# media_player_v0001a.net
KiCad netlist of a schematic drawn in EAGLE
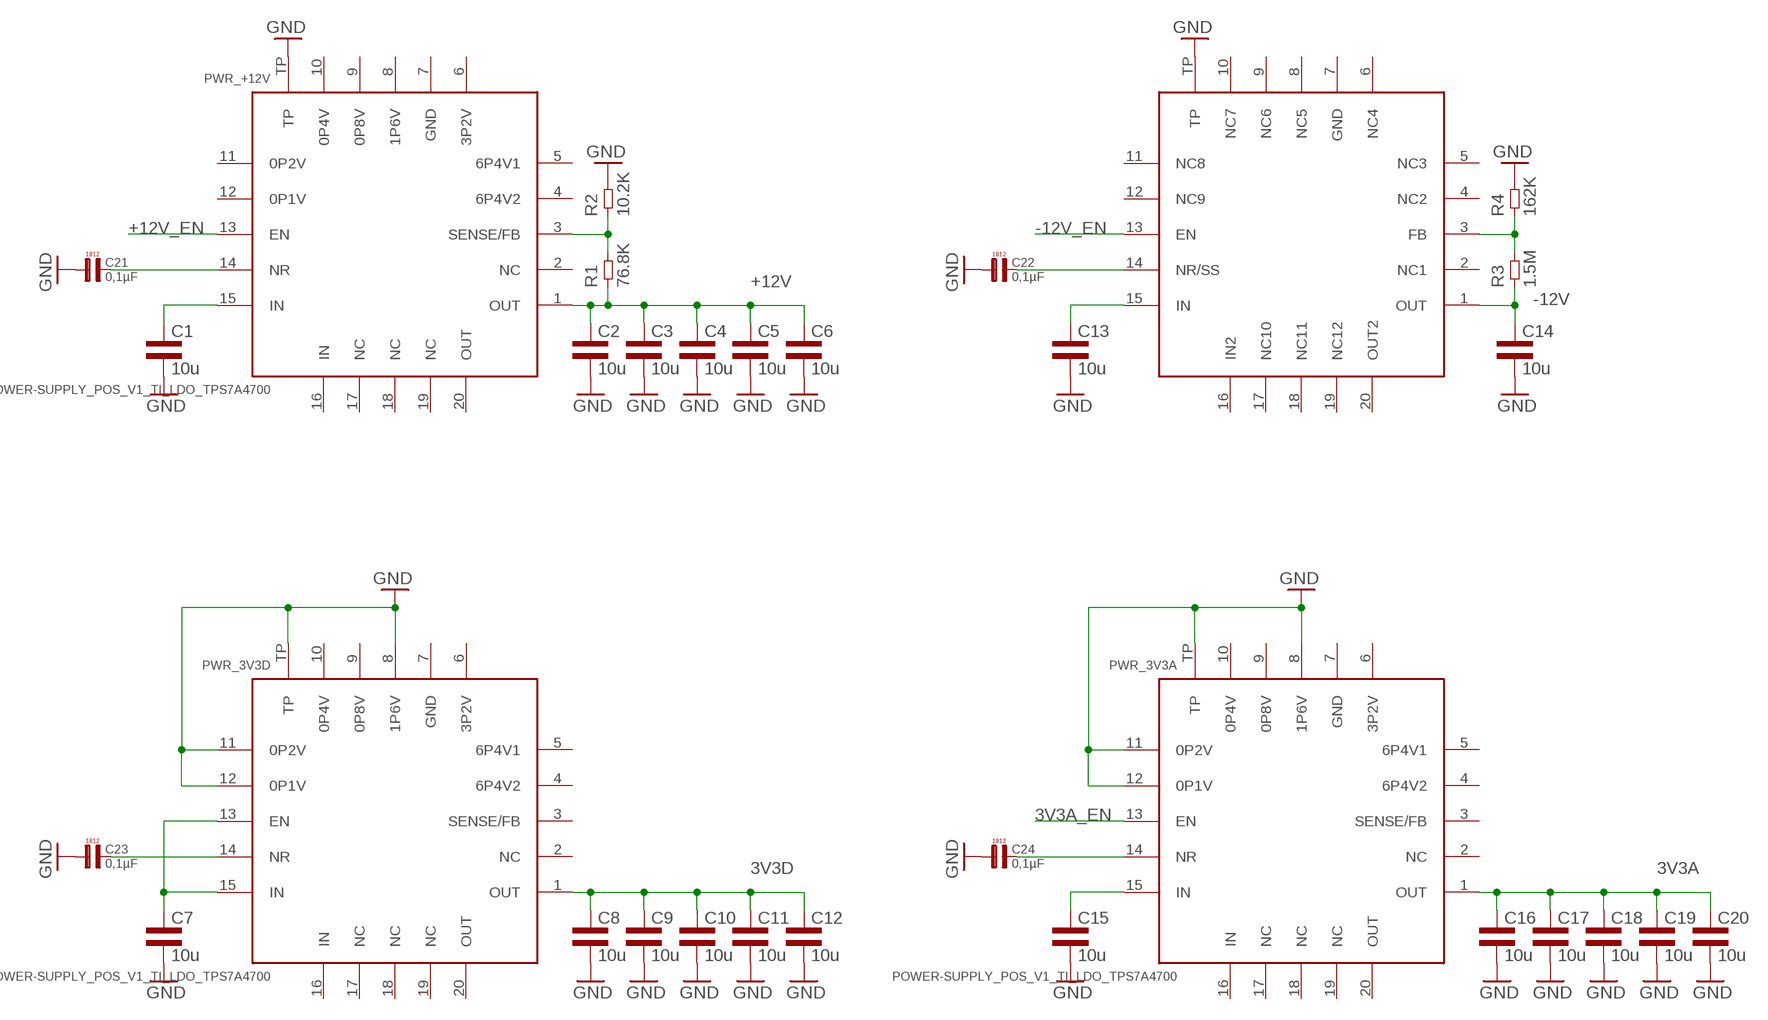
[diagram p0: schematic, sheet 1]
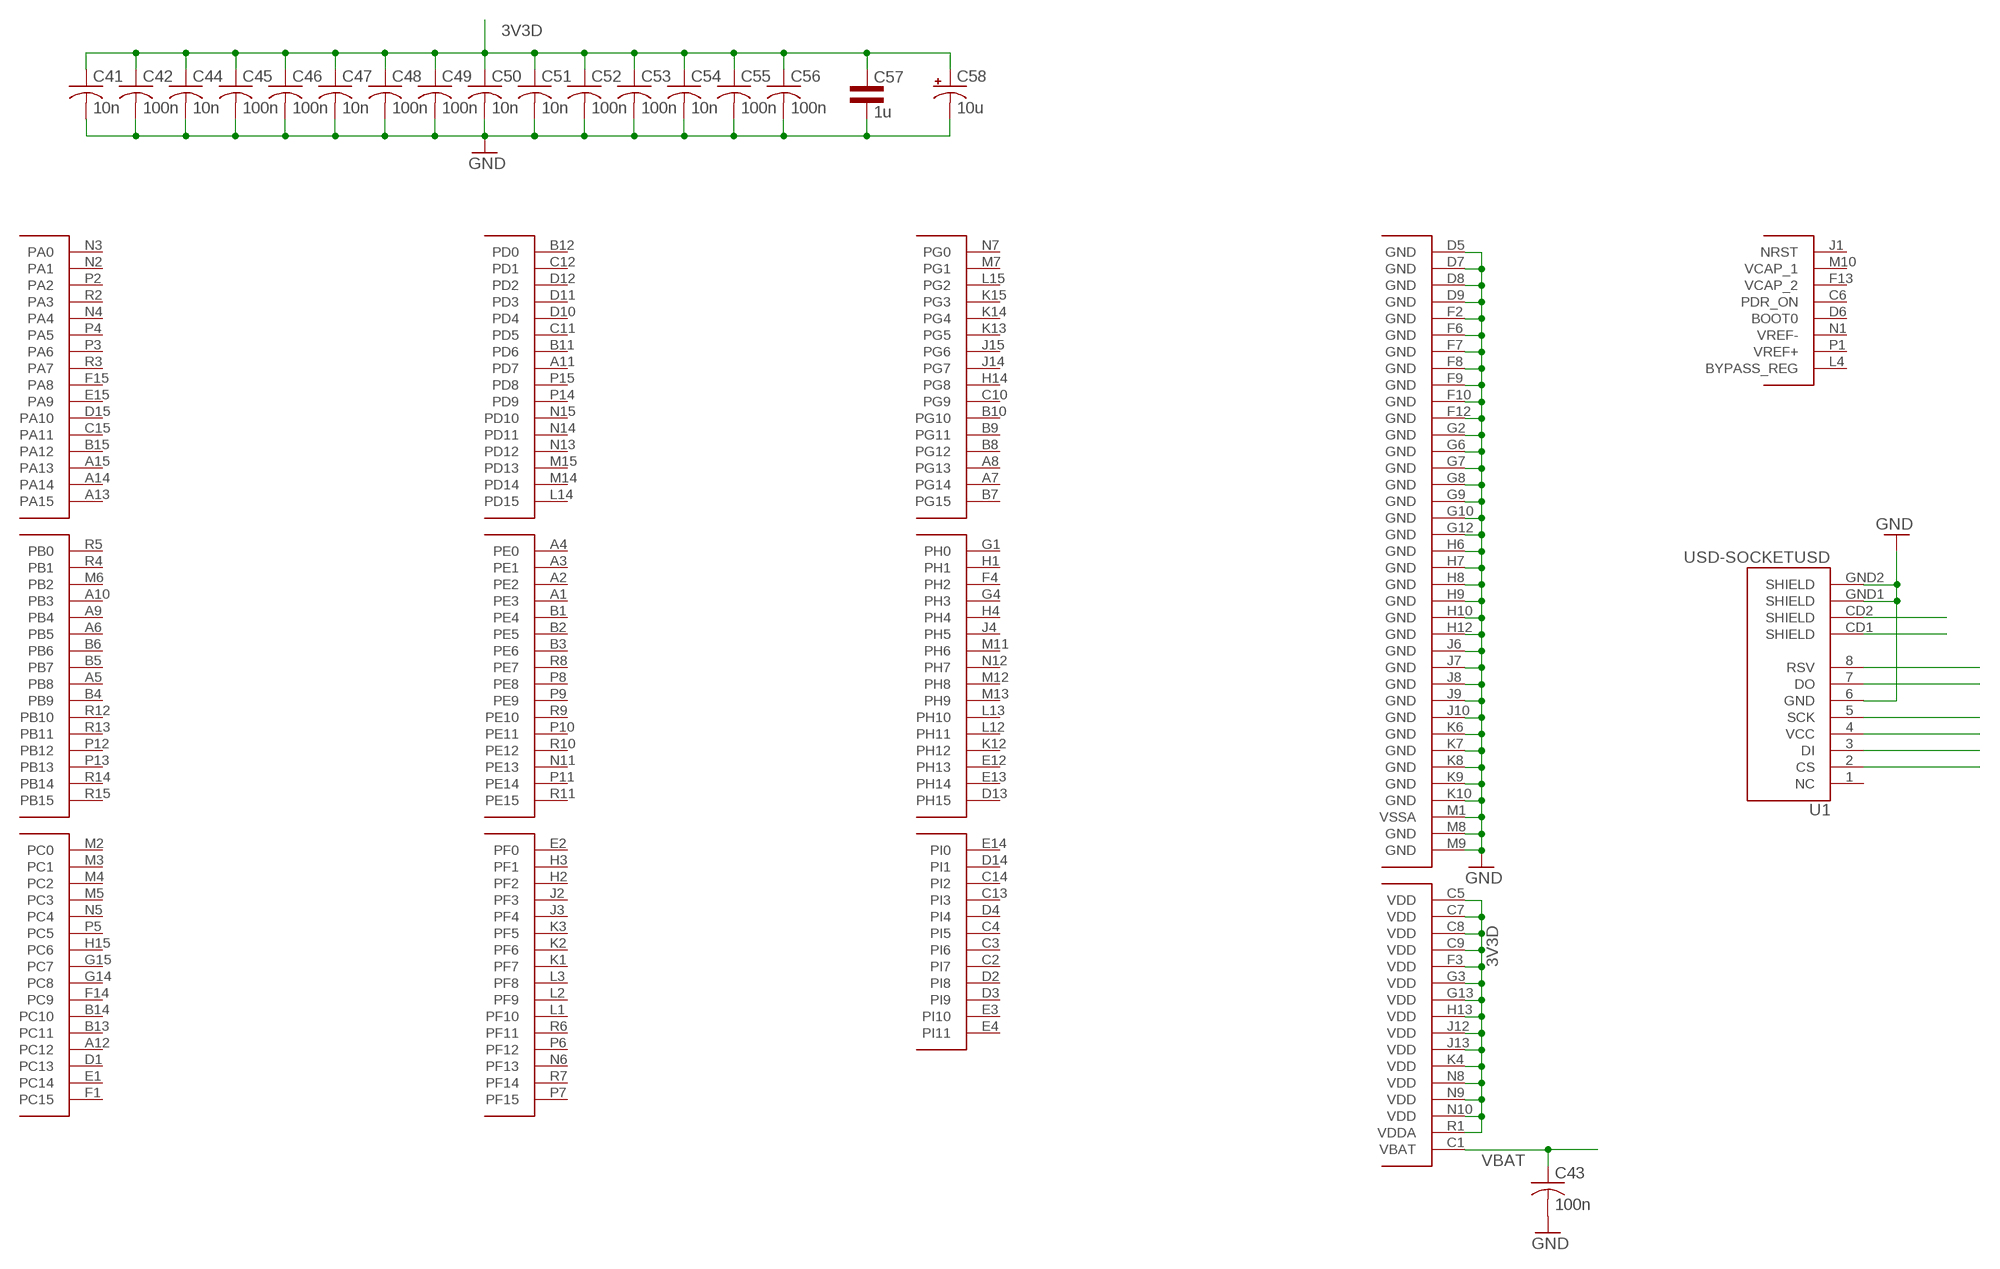
[diagram p1: schematic, sheet 2]
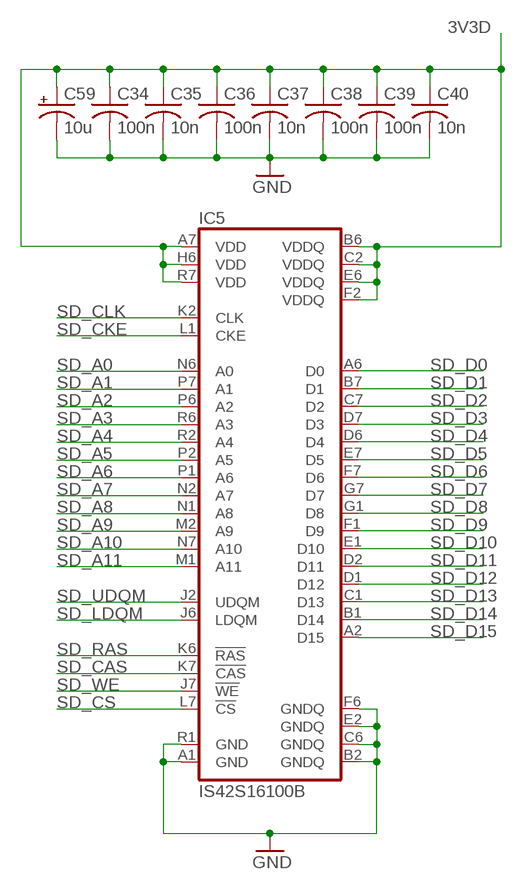
[diagram p2: schematic, sheet 3]
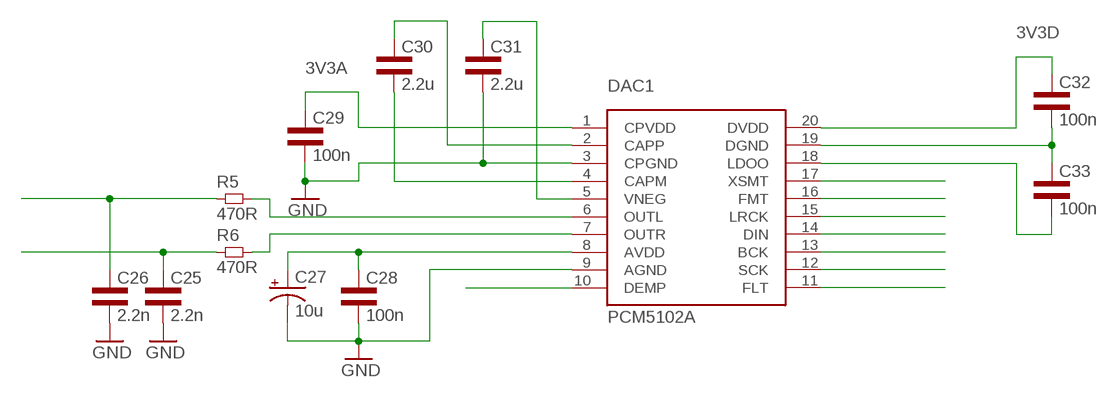
[diagram p3: schematic, sheet 4]
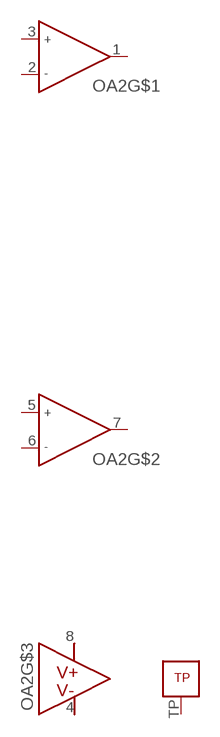
[diagram p4: schematic, sheet 5]
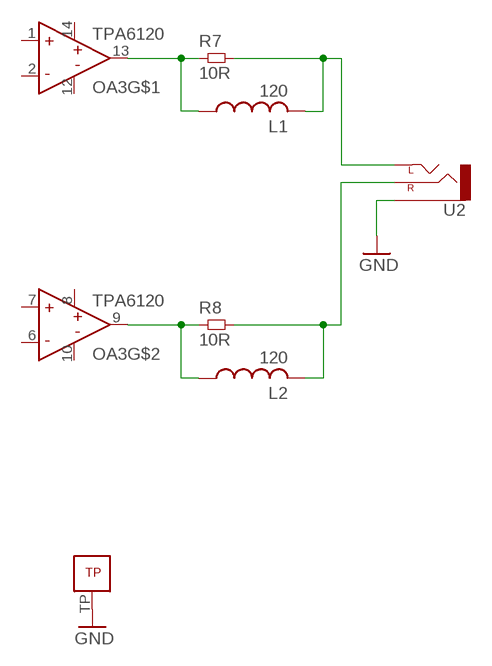
[diagram p5: schematic, sheet 6]

(export (version "E")
  (design (tool "Eeschema 10.0.6"))
  (components
    (comp (ref "C1")
      (value "10u")
      (footprint "eagle-import:0805L3")
      (libsource (lib "eagle-import") (part "CAP0805L3"))
    )
    (comp (ref "C2")
      (value "10u")
      (footprint "eagle-import:0805L3")
      (libsource (lib "eagle-import") (part "CAP0805L3"))
    )
    (comp (ref "C3")
      (value "10u")
      (footprint "eagle-import:0805L3")
      (libsource (lib "eagle-import") (part "CAP0805L3"))
    )
    (comp (ref "C4")
      (value "10u")
      (footprint "eagle-import:0805L3")
      (libsource (lib "eagle-import") (part "CAP0805L3"))
    )
    (comp (ref "C5")
      (value "10u")
      (footprint "eagle-import:0805L3")
      (libsource (lib "eagle-import") (part "CAP0805L3"))
    )
    (comp (ref "C6")
      (value "10u")
      (footprint "eagle-import:0805L3")
      (libsource (lib "eagle-import") (part "CAP0805L3"))
    )
    (comp (ref "C7")
      (value "10u")
      (footprint "eagle-import:0805L3")
      (libsource (lib "eagle-import") (part "CAP0805L3"))
    )
    (comp (ref "C8")
      (value "10u")
      (footprint "eagle-import:0805L3")
      (libsource (lib "eagle-import") (part "CAP0805L3"))
    )
    (comp (ref "C9")
      (value "10u")
      (footprint "eagle-import:0805L3")
      (libsource (lib "eagle-import") (part "CAP0805L3"))
    )
    (comp (ref "C10")
      (value "10u")
      (footprint "eagle-import:0805L3")
      (libsource (lib "eagle-import") (part "CAP0805L3"))
    )
    (comp (ref "C11")
      (value "10u")
      (footprint "eagle-import:0805L3")
      (libsource (lib "eagle-import") (part "CAP0805L3"))
    )
    (comp (ref "C12")
      (value "10u")
      (footprint "eagle-import:0805L3")
      (libsource (lib "eagle-import") (part "CAP0805L3"))
    )
    (comp (ref "C13")
      (value "10u")
      (footprint "eagle-import:0805L3")
      (libsource (lib "eagle-import") (part "CAP0805L3"))
    )
    (comp (ref "C14")
      (value "10u")
      (footprint "eagle-import:0805L3")
      (libsource (lib "eagle-import") (part "CAP0805L3"))
    )
    (comp (ref "C15")
      (value "10u")
      (footprint "eagle-import:0805L3")
      (libsource (lib "eagle-import") (part "CAP0805L3"))
    )
    (comp (ref "C16")
      (value "10u")
      (footprint "eagle-import:0805L3")
      (libsource (lib "eagle-import") (part "CAP0805L3"))
    )
    (comp (ref "C17")
      (value "10u")
      (footprint "eagle-import:0805L3")
      (libsource (lib "eagle-import") (part "CAP0805L3"))
    )
    (comp (ref "C18")
      (value "10u")
      (footprint "eagle-import:0805L3")
      (libsource (lib "eagle-import") (part "CAP0805L3"))
    )
    (comp (ref "C19")
      (value "10u")
      (footprint "eagle-import:0805L3")
      (libsource (lib "eagle-import") (part "CAP0805L3"))
    )
    (comp (ref "C20")
      (value "10u")
      (footprint "eagle-import:0805L3")
      (libsource (lib "eagle-import") (part "CAP0805L3"))
    )
    (comp (ref "C21")
      (value "0,1µF")
      (footprint "eagle-import:L4,8")
      (libsource (lib "eagle-import") (part "0,1µF"))
    )
    (comp (ref "C22")
      (value "0,1µF")
      (footprint "eagle-import:L4,8")
      (libsource (lib "eagle-import") (part "0,1µF"))
    )
    (comp (ref "C23")
      (value "0,1µF")
      (footprint "eagle-import:L4,8")
      (libsource (lib "eagle-import") (part "0,1µF"))
    )
    (comp (ref "C24")
      (value "0,1µF")
      (footprint "eagle-import:L4,8")
      (libsource (lib "eagle-import") (part "0,1µF"))
    )
    (comp (ref "PWR_+12V")
      (value "POWER-SUPPLY_POS_V1_TI_LDO_TPS7A4700")
      (footprint "eagle-import:POWER-SUPPLY_POS_V1_TI_LDO_VQFN-20")
      (libsource (lib "eagle-import") (part "POWER-SUPPLY_POS_V1_TI_LDO_TPS7A4700"))
    )
    (comp (ref "PWR_-12V")
      (value "POWER-SUPPLY_POS_V1_TI_LDO_TPS7A3301RGWT")
      (footprint "eagle-import:POWER-SUPPLY_POS_V1_TI_LDO_VQFN-20")
      (libsource (lib "eagle-import") (part "POWER-SUPPLY_POS_V1_TI_LDO_TPS7A3301RGWT"))
    )
    (comp (ref "PWR_3V3A")
      (value "POWER-SUPPLY_POS_V1_TI_LDO_TPS7A4700")
      (footprint "eagle-import:POWER-SUPPLY_POS_V1_TI_LDO_VQFN-20")
      (libsource (lib "eagle-import") (part "POWER-SUPPLY_POS_V1_TI_LDO_TPS7A4700"))
    )
    (comp (ref "PWR_3V3D")
      (value "POWER-SUPPLY_POS_V1_TI_LDO_TPS7A4700")
      (footprint "eagle-import:POWER-SUPPLY_POS_V1_TI_LDO_VQFN-20")
      (libsource (lib "eagle-import") (part "POWER-SUPPLY_POS_V1_TI_LDO_TPS7A4700"))
    )
    (comp (ref "R1")
      (value "76.8K")
      (footprint "eagle-import:0603L3")
      (libsource (lib "eagle-import") (part "RES0603L3"))
    )
    (comp (ref "R2")
      (value "10.2K")
      (footprint "eagle-import:0603L3")
      (libsource (lib "eagle-import") (part "RES0603L3"))
    )
    (comp (ref "R3")
      (value "1.5M")
      (footprint "eagle-import:0603L3")
      (libsource (lib "eagle-import") (part "RES0603L3"))
    )
    (comp (ref "R4")
      (value "162K")
      (footprint "eagle-import:0603L3")
      (libsource (lib "eagle-import") (part "RES0603L3"))
    )
    (comp (ref "OA2")
      (value "OPA1612")
      (footprint "eagle-import:S-PWSON-N8")
      (libsource (lib "eagle-import") (part "OPA1612"))
    )
    (comp (ref "C25")
      (value "2.2n")
      (footprint "eagle-import:0805L3")
      (libsource (lib "eagle-import") (part "CAP0805L3"))
    )
    (comp (ref "C26")
      (value "2.2n")
      (footprint "eagle-import:0805L3")
      (libsource (lib "eagle-import") (part "CAP0805L3"))
    )
    (comp (ref "C27")
      (value "10u")
      (footprint "eagle-import:A_3216-18R")
      (libsource (lib "eagle-import") (part "CPOL-USA/3216-18R"))
    )
    (comp (ref "C28")
      (value "100n")
      (footprint "eagle-import:0603L3")
      (libsource (lib "eagle-import") (part "CAP0603L3"))
    )
    (comp (ref "C29")
      (value "100n")
      (footprint "eagle-import:0603L3")
      (libsource (lib "eagle-import") (part "CAP0603L3"))
    )
    (comp (ref "C30")
      (value "2.2u")
      (footprint "eagle-import:0805L3")
      (libsource (lib "eagle-import") (part "CAP0805L3"))
    )
    (comp (ref "C31")
      (value "2.2u")
      (footprint "eagle-import:0805L3")
      (libsource (lib "eagle-import") (part "CAP0805L3"))
    )
    (comp (ref "C32")
      (value "100n")
      (footprint "eagle-import:0603L3")
      (libsource (lib "eagle-import") (part "CAP0603L3"))
    )
    (comp (ref "C33")
      (value "100n")
      (footprint "eagle-import:0603L3")
      (libsource (lib "eagle-import") (part "CAP0603L3"))
    )
    (comp (ref "DAC1")
      (value "PCM5102A")
      (footprint "eagle-import:R-PDSO-G20_65")
      (libsource (lib "eagle-import") (part "PCM5102A"))
    )
    (comp (ref "R5")
      (value "470R")
      (footprint "eagle-import:0805L3")
      (libsource (lib "eagle-import") (part "RES0805L3"))
    )
    (comp (ref "R6")
      (value "470R")
      (footprint "eagle-import:0805L3")
      (libsource (lib "eagle-import") (part "RES0805L3"))
    )
    (comp (ref "L1")
      (value "120")
      (footprint "eagle-import:L2012C")
      (libsource (lib "eagle-import") (part "L-USL2012C"))
    )
    (comp (ref "L2")
      (value "120")
      (footprint "eagle-import:L2012C")
      (libsource (lib "eagle-import") (part "L-USL2012C"))
    )
    (comp (ref "OA3")
      (value "TPA6120QFN")
      (footprint "eagle-import:S-PVQFN-N14")
      (libsource (lib "eagle-import") (part "TPA6120QFN"))
    )
    (comp (ref "R7")
      (value "10R")
      (footprint "eagle-import:0805L3")
      (libsource (lib "eagle-import") (part "RES0805L3"))
    )
    (comp (ref "R8")
      (value "10R")
      (footprint "eagle-import:0805L3")
      (libsource (lib "eagle-import") (part "RES0805L3"))
    )
    (comp (ref "U2")
      (value "AUDIO-JACKSMD2")
      (footprint "eagle-import:AUDIO-JACK-3.5MM-SMD")
      (libsource (lib "eagle-import") (part "AUDIO-JACKSMD2"))
    )
    (comp (ref "C41")
      (value "10n")
      (footprint "eagle-import:C0201")
      (libsource (lib "eagle-import") (part "C-USC0201"))
    )
    (comp (ref "C42")
      (value "100n")
      (footprint "eagle-import:C0201")
      (libsource (lib "eagle-import") (part "C-USC0201"))
    )
    (comp (ref "C43")
      (value "100n")
      (footprint "eagle-import:C0201")
      (libsource (lib "eagle-import") (part "C-USC0201"))
    )
    (comp (ref "C44")
      (value "10n")
      (footprint "eagle-import:C0201")
      (libsource (lib "eagle-import") (part "C-USC0201"))
    )
    (comp (ref "C45")
      (value "100n")
      (footprint "eagle-import:C0201")
      (libsource (lib "eagle-import") (part "C-USC0201"))
    )
    (comp (ref "C46")
      (value "100n")
      (footprint "eagle-import:C0201")
      (libsource (lib "eagle-import") (part "C-USC0201"))
    )
    (comp (ref "C47")
      (value "10n")
      (footprint "eagle-import:C0201")
      (libsource (lib "eagle-import") (part "C-USC0201"))
    )
    (comp (ref "C48")
      (value "100n")
      (footprint "eagle-import:C0201")
      (libsource (lib "eagle-import") (part "C-USC0201"))
    )
    (comp (ref "C49")
      (value "100n")
      (footprint "eagle-import:C0201")
      (libsource (lib "eagle-import") (part "C-USC0201"))
    )
    (comp (ref "C50")
      (value "10n")
      (footprint "eagle-import:C0201")
      (libsource (lib "eagle-import") (part "C-USC0201"))
    )
    (comp (ref "C51")
      (value "10n")
      (footprint "eagle-import:C0201")
      (libsource (lib "eagle-import") (part "C-USC0201"))
    )
    (comp (ref "C52")
      (value "100n")
      (footprint "eagle-import:C0201")
      (libsource (lib "eagle-import") (part "C-USC0201"))
    )
    (comp (ref "C53")
      (value "100n")
      (footprint "eagle-import:C0201")
      (libsource (lib "eagle-import") (part "C-USC0201"))
    )
    (comp (ref "C54")
      (value "10n")
      (footprint "eagle-import:C0201")
      (libsource (lib "eagle-import") (part "C-USC0201"))
    )
    (comp (ref "C55")
      (value "100n")
      (footprint "eagle-import:C0201")
      (libsource (lib "eagle-import") (part "C-USC0201"))
    )
    (comp (ref "C56")
      (value "100n")
      (footprint "eagle-import:C0201")
      (libsource (lib "eagle-import") (part "C-USC0201"))
    )
    (comp (ref "C57")
      (value "1u")
      (footprint "eagle-import:0805L3")
      (libsource (lib "eagle-import") (part "CAP0805L3"))
    )
    (comp (ref "C58")
      (value "10u")
      (footprint "eagle-import:A_3216-18R")
      (libsource (lib "eagle-import") (part "CPOL-USA/3216-18R"))
    )
    (comp (ref "U$1")
      (value "STM32_32BIT_MCU_STM32F407IG")
      (footprint "eagle-import:STM32_32BIT_MCU_UFBGA176+25")
      (libsource (lib "eagle-import") (part "STM32_32BIT_MCU_STM32F407IG"))
    )
    (comp (ref "U1")
      (value "USD-SOCKETUSD")
      (footprint "eagle-import:USD-SOCKET-PP")
      (libsource (lib "eagle-import") (part "USD-SOCKETUSD"))
    )
    (comp (ref "C34")
      (value "100n")
      (footprint "eagle-import:C0201")
      (libsource (lib "eagle-import") (part "C-USC0201"))
    )
    (comp (ref "C35")
      (value "10n")
      (footprint "eagle-import:C0201")
      (libsource (lib "eagle-import") (part "C-USC0201"))
    )
    (comp (ref "C36")
      (value "100n")
      (footprint "eagle-import:C0201")
      (libsource (lib "eagle-import") (part "C-USC0201"))
    )
    (comp (ref "C37")
      (value "10n")
      (footprint "eagle-import:C0201")
      (libsource (lib "eagle-import") (part "C-USC0201"))
    )
    (comp (ref "C38")
      (value "100n")
      (footprint "eagle-import:C0201")
      (libsource (lib "eagle-import") (part "C-USC0201"))
    )
    (comp (ref "C39")
      (value "100n")
      (footprint "eagle-import:C0201")
      (libsource (lib "eagle-import") (part "C-USC0201"))
    )
    (comp (ref "C40")
      (value "10n")
      (footprint "eagle-import:C0201")
      (libsource (lib "eagle-import") (part "C-USC0201"))
    )
    (comp (ref "C59")
      (value "10u")
      (footprint "eagle-import:A_3216-18R")
      (libsource (lib "eagle-import") (part "CPOL-USA/3216-18R"))
    )
    (comp (ref "IC5")
      (value "IS42S16100B")
      (footprint "eagle-import:MBGA60")
      (libsource (lib "eagle-import") (part "IS42S16100B"))
    )
  )
  (nets
    (net (code "1") (name "+12V_EN") (class "Default")
      (node (ref "PWR_+12V") (pin "13") (pinfunction "EN_13") (pintype "bidirectional"))
    )
    (net (code "2") (name "-12V_EN") (class "Default")
      (node (ref "PWR_-12V") (pin "13") (pinfunction "EN_13") (pintype "bidirectional"))
    )
    (net (code "3") (name "3V3A") (class "Default")
      (node (ref "C16") (pin "1") (pinfunction "1_1") (pintype "bidirectional"))
      (node (ref "C17") (pin "1") (pinfunction "1_1") (pintype "bidirectional"))
      (node (ref "C18") (pin "1") (pinfunction "1_1") (pintype "bidirectional"))
      (node (ref "C19") (pin "1") (pinfunction "1_1") (pintype "bidirectional"))
      (node (ref "C20") (pin "1") (pinfunction "1_1") (pintype "bidirectional"))
      (node (ref "C29") (pin "P$1") (pinfunction "1_P$1") (pintype "bidirectional"))
      (node (ref "DAC1") (pin "1") (pinfunction "CPVDD_1") (pintype "bidirectional"))
      (node (ref "PWR_3V3A") (pin "1") (pinfunction "OUT_1") (pintype "bidirectional"))
    )
    (net (code "4") (name "3V3A_EN") (class "Default")
      (node (ref "PWR_3V3A") (pin "13") (pinfunction "EN_13") (pintype "bidirectional"))
    )
    (net (code "5") (name "3V3D") (class "Default")
      (node (ref "C10") (pin "1") (pinfunction "1_1") (pintype "bidirectional"))
      (node (ref "C11") (pin "1") (pinfunction "1_1") (pintype "bidirectional"))
      (node (ref "C12") (pin "1") (pinfunction "1_1") (pintype "bidirectional"))
      (node (ref "C32") (pin "P$1") (pinfunction "1_P$1") (pintype "bidirectional"))
      (node (ref "C34") (pin "1") (pinfunction "1_1") (pintype "passive"))
      (node (ref "C35") (pin "1") (pinfunction "1_1") (pintype "passive"))
      (node (ref "C36") (pin "1") (pinfunction "1_1") (pintype "passive"))
      (node (ref "C37") (pin "1") (pinfunction "1_1") (pintype "passive"))
      (node (ref "C38") (pin "1") (pinfunction "1_1") (pintype "passive"))
      (node (ref "C39") (pin "1") (pinfunction "1_1") (pintype "passive"))
      (node (ref "C40") (pin "1") (pinfunction "1_1") (pintype "passive"))
      (node (ref "C41") (pin "1") (pinfunction "1_1") (pintype "passive"))
      (node (ref "C42") (pin "1") (pinfunction "1_1") (pintype "passive"))
      (node (ref "C44") (pin "1") (pinfunction "1_1") (pintype "passive"))
      (node (ref "C45") (pin "1") (pinfunction "1_1") (pintype "passive"))
      (node (ref "C46") (pin "1") (pinfunction "1_1") (pintype "passive"))
      (node (ref "C47") (pin "1") (pinfunction "1_1") (pintype "passive"))
      (node (ref "C48") (pin "1") (pinfunction "1_1") (pintype "passive"))
      (node (ref "C49") (pin "1") (pinfunction "1_1") (pintype "passive"))
      (node (ref "C50") (pin "1") (pinfunction "1_1") (pintype "passive"))
      (node (ref "C51") (pin "1") (pinfunction "1_1") (pintype "passive"))
      (node (ref "C52") (pin "1") (pinfunction "1_1") (pintype "passive"))
      (node (ref "C53") (pin "1") (pinfunction "1_1") (pintype "passive"))
      (node (ref "C54") (pin "1") (pinfunction "1_1") (pintype "passive"))
      (node (ref "C55") (pin "1") (pinfunction "1_1") (pintype "passive"))
      (node (ref "C56") (pin "1") (pinfunction "1_1") (pintype "passive"))
      (node (ref "C57") (pin "1") (pinfunction "1_1") (pintype "bidirectional"))
      (node (ref "C58") (pin "+") (pinfunction "+_+") (pintype "passive"))
      (node (ref "C59") (pin "+") (pinfunction "+_+") (pintype "passive"))
      (node (ref "C8") (pin "1") (pinfunction "1_1") (pintype "bidirectional"))
      (node (ref "C9") (pin "1") (pinfunction "1_1") (pintype "bidirectional"))
      (node (ref "DAC1") (pin "20") (pinfunction "DVDD_20") (pintype "bidirectional"))
      (node (ref "IC5") (pin "A7") (pinfunction "VDD_A7") (pintype "power_in"))
      (node (ref "IC5") (pin "B6") (pinfunction "VDDQ_B6") (pintype "power_in"))
      (node (ref "IC5") (pin "C2") (pinfunction "VDDQ_C2") (pintype "power_in"))
      (node (ref "IC5") (pin "E6") (pinfunction "VDDQ_E6") (pintype "power_in"))
      (node (ref "IC5") (pin "F2") (pinfunction "VDDQ_F2") (pintype "power_in"))
      (node (ref "IC5") (pin "H6") (pinfunction "VDD_H6") (pintype "power_in"))
      (node (ref "IC5") (pin "R7") (pinfunction "VDD_R7") (pintype "power_in"))
      (node (ref "PWR_3V3D") (pin "1") (pinfunction "OUT_1") (pintype "bidirectional"))
      (node (ref "U$1") (pin "C5") (pinfunction "VDD_C5") (pintype "bidirectional"))
      (node (ref "U$1") (pin "C7") (pinfunction "VDD_C7") (pintype "bidirectional"))
      (node (ref "U$1") (pin "C8") (pinfunction "VDD_C8") (pintype "bidirectional"))
      (node (ref "U$1") (pin "C9") (pinfunction "VDD_C9") (pintype "bidirectional"))
      (node (ref "U$1") (pin "F3") (pinfunction "VDD_F3") (pintype "bidirectional"))
      (node (ref "U$1") (pin "G13") (pinfunction "VDD_G13") (pintype "bidirectional"))
      (node (ref "U$1") (pin "G3") (pinfunction "VDD_G3") (pintype "bidirectional"))
      (node (ref "U$1") (pin "H13") (pinfunction "VDD_H13") (pintype "bidirectional"))
      (node (ref "U$1") (pin "J12") (pinfunction "VDD_J12") (pintype "bidirectional"))
      (node (ref "U$1") (pin "J13") (pinfunction "VDD_J13") (pintype "bidirectional"))
      (node (ref "U$1") (pin "K4") (pinfunction "VDD_K4") (pintype "bidirectional"))
      (node (ref "U$1") (pin "N10") (pinfunction "VDD_N10") (pintype "bidirectional"))
      (node (ref "U$1") (pin "N8") (pinfunction "VDD_N8") (pintype "bidirectional"))
      (node (ref "U$1") (pin "N9") (pinfunction "VDD_N9") (pintype "bidirectional"))
      (node (ref "U$1") (pin "R1") (pinfunction "VDDA_R1") (pintype "bidirectional"))
    )
    (net (code "6") (name "GND") (class "Default")
      (node (ref "C1") (pin "2") (pinfunction "2_2") (pintype "bidirectional"))
      (node (ref "C10") (pin "2") (pinfunction "2_2") (pintype "bidirectional"))
      (node (ref "C11") (pin "2") (pinfunction "2_2") (pintype "bidirectional"))
      (node (ref "C12") (pin "2") (pinfunction "2_2") (pintype "bidirectional"))
      (node (ref "C13") (pin "2") (pinfunction "2_2") (pintype "bidirectional"))
      (node (ref "C14") (pin "2") (pinfunction "2_2") (pintype "bidirectional"))
      (node (ref "C15") (pin "2") (pinfunction "2_2") (pintype "bidirectional"))
      (node (ref "C16") (pin "2") (pinfunction "2_2") (pintype "bidirectional"))
      (node (ref "C17") (pin "2") (pinfunction "2_2") (pintype "bidirectional"))
      (node (ref "C18") (pin "2") (pinfunction "2_2") (pintype "bidirectional"))
      (node (ref "C19") (pin "2") (pinfunction "2_2") (pintype "bidirectional"))
      (node (ref "C2") (pin "2") (pinfunction "2_2") (pintype "bidirectional"))
      (node (ref "C20") (pin "2") (pinfunction "2_2") (pintype "bidirectional"))
      (node (ref "C21") (pin "P$1") (pinfunction "1_P$1") (pintype "passive"))
      (node (ref "C22") (pin "P$1") (pinfunction "1_P$1") (pintype "passive"))
      (node (ref "C23") (pin "P$1") (pinfunction "1_P$1") (pintype "passive"))
      (node (ref "C24") (pin "P$1") (pinfunction "1_P$1") (pintype "passive"))
      (node (ref "C25") (pin "2") (pinfunction "2_2") (pintype "bidirectional"))
      (node (ref "C26") (pin "2") (pinfunction "2_2") (pintype "bidirectional"))
      (node (ref "C27") (pin "-") (pinfunction "-_-") (pintype "passive"))
      (node (ref "C28") (pin "P$2") (pinfunction "2_P$2") (pintype "bidirectional"))
      (node (ref "C29") (pin "P$2") (pinfunction "2_P$2") (pintype "bidirectional"))
      (node (ref "C3") (pin "2") (pinfunction "2_2") (pintype "bidirectional"))
      (node (ref "C31") (pin "2") (pinfunction "2_2") (pintype "bidirectional"))
      (node (ref "C34") (pin "2") (pinfunction "2_2") (pintype "passive"))
      (node (ref "C35") (pin "2") (pinfunction "2_2") (pintype "passive"))
      (node (ref "C36") (pin "2") (pinfunction "2_2") (pintype "passive"))
      (node (ref "C37") (pin "2") (pinfunction "2_2") (pintype "passive"))
      (node (ref "C38") (pin "2") (pinfunction "2_2") (pintype "passive"))
      (node (ref "C39") (pin "2") (pinfunction "2_2") (pintype "passive"))
      (node (ref "C4") (pin "2") (pinfunction "2_2") (pintype "bidirectional"))
      (node (ref "C40") (pin "2") (pinfunction "2_2") (pintype "passive"))
      (node (ref "C41") (pin "2") (pinfunction "2_2") (pintype "passive"))
      (node (ref "C42") (pin "2") (pinfunction "2_2") (pintype "passive"))
      (node (ref "C43") (pin "2") (pinfunction "2_2") (pintype "passive"))
      (node (ref "C44") (pin "2") (pinfunction "2_2") (pintype "passive"))
      (node (ref "C45") (pin "2") (pinfunction "2_2") (pintype "passive"))
      (node (ref "C46") (pin "2") (pinfunction "2_2") (pintype "passive"))
      (node (ref "C47") (pin "2") (pinfunction "2_2") (pintype "passive"))
      (node (ref "C48") (pin "2") (pinfunction "2_2") (pintype "passive"))
      (node (ref "C49") (pin "2") (pinfunction "2_2") (pintype "passive"))
      (node (ref "C5") (pin "2") (pinfunction "2_2") (pintype "bidirectional"))
      (node (ref "C50") (pin "2") (pinfunction "2_2") (pintype "passive"))
      (node (ref "C51") (pin "2") (pinfunction "2_2") (pintype "passive"))
      (node (ref "C52") (pin "2") (pinfunction "2_2") (pintype "passive"))
      (node (ref "C53") (pin "2") (pinfunction "2_2") (pintype "passive"))
      (node (ref "C54") (pin "2") (pinfunction "2_2") (pintype "passive"))
      (node (ref "C55") (pin "2") (pinfunction "2_2") (pintype "passive"))
      (node (ref "C56") (pin "2") (pinfunction "2_2") (pintype "passive"))
      (node (ref "C57") (pin "2") (pinfunction "2_2") (pintype "bidirectional"))
      (node (ref "C58") (pin "-") (pinfunction "-_-") (pintype "passive"))
      (node (ref "C59") (pin "-") (pinfunction "-_-") (pintype "passive"))
      (node (ref "C6") (pin "2") (pinfunction "2_2") (pintype "bidirectional"))
      (node (ref "C7") (pin "2") (pinfunction "2_2") (pintype "bidirectional"))
      (node (ref "C8") (pin "2") (pinfunction "2_2") (pintype "bidirectional"))
      (node (ref "C9") (pin "2") (pinfunction "2_2") (pintype "bidirectional"))
      (node (ref "DAC1") (pin "3") (pinfunction "CPGND_3") (pintype "bidirectional"))
      (node (ref "DAC1") (pin "9") (pinfunction "AGND_9") (pintype "bidirectional"))
      (node (ref "IC5") (pin "A1") (pinfunction "GND_A1") (pintype "power_in"))
      (node (ref "IC5") (pin "B2") (pinfunction "GNDQ_B2") (pintype "power_in"))
      (node (ref "IC5") (pin "C6") (pinfunction "GNDQ_C6") (pintype "power_in"))
      (node (ref "IC5") (pin "E2") (pinfunction "GNDQ_E2") (pintype "power_in"))
      (node (ref "IC5") (pin "F6") (pinfunction "GNDQ_F6") (pintype "power_in"))
      (node (ref "IC5") (pin "R1") (pinfunction "GND_R1") (pintype "power_in"))
      (node (ref "OA3") (pin "TP") (pinfunction "TP_TP") (pintype "bidirectional"))
      (node (ref "PWR_+12V") (pin "TP") (pinfunction "TP_TP") (pintype "bidirectional"))
      (node (ref "PWR_-12V") (pin "TP") (pinfunction "TP_TP") (pintype "bidirectional"))
      (node (ref "PWR_3V3A") (pin "11") (pinfunction "0P2V_11") (pintype "bidirectional"))
      (node (ref "PWR_3V3A") (pin "12") (pinfunction "0P1V_12") (pintype "bidirectional"))
      (node (ref "PWR_3V3A") (pin "8") (pinfunction "1P6V_8") (pintype "bidirectional"))
      (node (ref "PWR_3V3A") (pin "TP") (pinfunction "TP_TP") (pintype "bidirectional"))
      (node (ref "PWR_3V3D") (pin "11") (pinfunction "0P2V_11") (pintype "bidirectional"))
      (node (ref "PWR_3V3D") (pin "12") (pinfunction "0P1V_12") (pintype "bidirectional"))
      (node (ref "PWR_3V3D") (pin "8") (pinfunction "1P6V_8") (pintype "bidirectional"))
      (node (ref "PWR_3V3D") (pin "TP") (pinfunction "TP_TP") (pintype "bidirectional"))
      (node (ref "R2") (pin "P$2") (pinfunction "2_P$2") (pintype "bidirectional"))
      (node (ref "R4") (pin "P$2") (pinfunction "2_P$2") (pintype "bidirectional"))
      (node (ref "U$1") (pin "D5") (pinfunction "GND_D5") (pintype "bidirectional"))
      (node (ref "U$1") (pin "D7") (pinfunction "GND_D7") (pintype "bidirectional"))
      (node (ref "U$1") (pin "D8") (pinfunction "GND_D8") (pintype "bidirectional"))
      (node (ref "U$1") (pin "D9") (pinfunction "GND_D9") (pintype "bidirectional"))
      (node (ref "U$1") (pin "F10") (pinfunction "GND_F10") (pintype "bidirectional"))
      (node (ref "U$1") (pin "F12") (pinfunction "GND_F12") (pintype "bidirectional"))
      (node (ref "U$1") (pin "F2") (pinfunction "GND_F2") (pintype "bidirectional"))
      (node (ref "U$1") (pin "F6") (pinfunction "GND_F6") (pintype "bidirectional"))
      (node (ref "U$1") (pin "F7") (pinfunction "GND_F7") (pintype "bidirectional"))
      (node (ref "U$1") (pin "F8") (pinfunction "GND_F8") (pintype "bidirectional"))
      (node (ref "U$1") (pin "F9") (pinfunction "GND_F9") (pintype "bidirectional"))
      (node (ref "U$1") (pin "G10") (pinfunction "GND_G10") (pintype "bidirectional"))
      (node (ref "U$1") (pin "G12") (pinfunction "GND_G12") (pintype "bidirectional"))
      (node (ref "U$1") (pin "G2") (pinfunction "GND_G2") (pintype "bidirectional"))
      (node (ref "U$1") (pin "G6") (pinfunction "GND_G6") (pintype "bidirectional"))
      (node (ref "U$1") (pin "G7") (pinfunction "GND_G7") (pintype "bidirectional"))
      (node (ref "U$1") (pin "G8") (pinfunction "GND_G8") (pintype "bidirectional"))
      (node (ref "U$1") (pin "G9") (pinfunction "GND_G9") (pintype "bidirectional"))
      (node (ref "U$1") (pin "H10") (pinfunction "GND_H10") (pintype "bidirectional"))
      (node (ref "U$1") (pin "H12") (pinfunction "GND_H12") (pintype "bidirectional"))
      (node (ref "U$1") (pin "H6") (pinfunction "GND_H6") (pintype "bidirectional"))
      (node (ref "U$1") (pin "H7") (pinfunction "GND_H7") (pintype "bidirectional"))
      (node (ref "U$1") (pin "H8") (pinfunction "GND_H8") (pintype "bidirectional"))
      (node (ref "U$1") (pin "H9") (pinfunction "GND_H9") (pintype "bidirectional"))
      (node (ref "U$1") (pin "J10") (pinfunction "GND_J10") (pintype "bidirectional"))
      (node (ref "U$1") (pin "J6") (pinfunction "GND_J6") (pintype "bidirectional"))
      (node (ref "U$1") (pin "J7") (pinfunction "GND_J7") (pintype "bidirectional"))
      (node (ref "U$1") (pin "J8") (pinfunction "GND_J8") (pintype "bidirectional"))
      (node (ref "U$1") (pin "J9") (pinfunction "GND_J9") (pintype "bidirectional"))
      (node (ref "U$1") (pin "K10") (pinfunction "GND_K10") (pintype "bidirectional"))
      (node (ref "U$1") (pin "K6") (pinfunction "GND_K6") (pintype "bidirectional"))
      (node (ref "U$1") (pin "K7") (pinfunction "GND_K7") (pintype "bidirectional"))
      (node (ref "U$1") (pin "K8") (pinfunction "GND_K8") (pintype "bidirectional"))
      (node (ref "U$1") (pin "K9") (pinfunction "GND_K9") (pintype "bidirectional"))
      (node (ref "U$1") (pin "M1") (pinfunction "VSSA_M1") (pintype "bidirectional"))
      (node (ref "U$1") (pin "M8") (pinfunction "GND_M8") (pintype "bidirectional"))
      (node (ref "U$1") (pin "M9") (pinfunction "GND_M9") (pintype "bidirectional"))
      (node (ref "U1") (pin "6") (pinfunction "GND_6") (pintype "bidirectional"))
      (node (ref "U1") (pin "GND1") (pinfunction "SHIELD_GND1") (pintype "bidirectional"))
      (node (ref "U1") (pin "GND2") (pinfunction "SHIELD_GND2") (pintype "bidirectional"))
      (node (ref "U2") (pin "SLEEVE") (pinfunction "SLEEVE_SLEEVE") (pintype "bidirectional"))
    )
    (net (code "7") (name "Net-(C21-2)") (class "Default")
      (node (ref "C21") (pin "P$2") (pinfunction "2_P$2") (pintype "passive"))
      (node (ref "PWR_+12V") (pin "14") (pinfunction "NR_14") (pintype "bidirectional"))
    )
    (net (code "8") (name "Net-(C22-2)") (class "Default")
      (node (ref "C22") (pin "P$2") (pinfunction "2_P$2") (pintype "passive"))
      (node (ref "PWR_-12V") (pin "14") (pinfunction "NR/SS_14") (pintype "bidirectional"))
    )
    (net (code "9") (name "Net-(C23-2)") (class "Default")
      (node (ref "C23") (pin "P$2") (pinfunction "2_P$2") (pintype "passive"))
      (node (ref "PWR_3V3D") (pin "14") (pinfunction "NR_14") (pintype "bidirectional"))
    )
    (net (code "10") (name "Net-(C24-2)") (class "Default")
      (node (ref "C24") (pin "P$2") (pinfunction "2_P$2") (pintype "passive"))
      (node (ref "PWR_3V3A") (pin "14") (pinfunction "NR_14") (pintype "bidirectional"))
    )
    (net (code "11") (name "Net-(C25-Pad1)") (class "Default")
      (node (ref "C25") (pin "1") (pinfunction "1_1") (pintype "bidirectional"))
      (node (ref "R6") (pin "1") (pinfunction "1_1") (pintype "bidirectional"))
    )
    (net (code "12") (name "Net-(C26-Pad1)") (class "Default")
      (node (ref "C26") (pin "1") (pinfunction "1_1") (pintype "bidirectional"))
      (node (ref "R5") (pin "1") (pinfunction "1_1") (pintype "bidirectional"))
    )
    (net (code "13") (name "Net-(C28-1)") (class "Default")
      (node (ref "C27") (pin "+") (pinfunction "+_+") (pintype "passive"))
      (node (ref "C28") (pin "P$1") (pinfunction "1_P$1") (pintype "bidirectional"))
      (node (ref "DAC1") (pin "8") (pinfunction "AVDD_8") (pintype "bidirectional"))
    )
    (net (code "14") (name "Net-(C32-2)") (class "Default")
      (node (ref "C32") (pin "P$2") (pinfunction "2_P$2") (pintype "bidirectional"))
      (node (ref "C33") (pin "P$1") (pinfunction "1_P$1") (pintype "bidirectional"))
      (node (ref "DAC1") (pin "19") (pinfunction "DGND_19") (pintype "bidirectional"))
    )
    (net (code "15") (name "Net-(C33-2)") (class "Default")
      (node (ref "C33") (pin "P$2") (pinfunction "2_P$2") (pintype "bidirectional"))
      (node (ref "DAC1") (pin "18") (pinfunction "LDOO_18") (pintype "bidirectional"))
    )
    (net (code "16") (name "Net-(DAC1-CAPM)") (class "Default")
      (node (ref "C30") (pin "2") (pinfunction "2_2") (pintype "bidirectional"))
      (node (ref "DAC1") (pin "4") (pinfunction "CAPM_4") (pintype "bidirectional"))
    )
    (net (code "17") (name "Net-(DAC1-CAPP)") (class "Default")
      (node (ref "C30") (pin "1") (pinfunction "1_1") (pintype "bidirectional"))
      (node (ref "DAC1") (pin "2") (pinfunction "CAPP_2") (pintype "bidirectional"))
    )
    (net (code "18") (name "Net-(DAC1-OUTL)") (class "Default")
      (node (ref "DAC1") (pin "6") (pinfunction "OUTL_6") (pintype "bidirectional"))
      (node (ref "R5") (pin "2") (pinfunction "2_2") (pintype "bidirectional"))
    )
    (net (code "19") (name "Net-(DAC1-OUTR)") (class "Default")
      (node (ref "DAC1") (pin "7") (pinfunction "OUTR_7") (pintype "bidirectional"))
      (node (ref "R6") (pin "2") (pinfunction "2_2") (pintype "bidirectional"))
    )
    (net (code "20") (name "Net-(DAC1-VNEG)") (class "Default")
      (node (ref "C31") (pin "1") (pinfunction "1_1") (pintype "bidirectional"))
      (node (ref "DAC1") (pin "5") (pinfunction "VNEG_5") (pintype "bidirectional"))
    )
    (net (code "21") (name "Net-(OA3A-OUT)") (class "Default")
      (node (ref "L1") (pin "1") (pinfunction "1_1") (pintype "passive"))
      (node (ref "OA3") (pin "13") (pinfunction "OUT_13") (pintype "bidirectional"))
      (node (ref "R7") (pin "1") (pinfunction "1_1") (pintype "bidirectional"))
    )
    (net (code "22") (name "Net-(OA3B-OUT)") (class "Default")
      (node (ref "L2") (pin "1") (pinfunction "1_1") (pintype "passive"))
      (node (ref "OA3") (pin "9") (pinfunction "OUT_9") (pintype "bidirectional"))
      (node (ref "R8") (pin "1") (pinfunction "1_1") (pintype "bidirectional"))
    )
    (net (code "23") (name "Net-(PWR_+12V-SENSE{slash}FB)") (class "Default")
      (node (ref "PWR_+12V") (pin "3") (pinfunction "SENSE/FB_3") (pintype "bidirectional"))
      (node (ref "R1") (pin "P$2") (pinfunction "2_P$2") (pintype "bidirectional"))
      (node (ref "R2") (pin "P$1") (pinfunction "1_P$1") (pintype "bidirectional"))
    )
    (net (code "24") (name "Net-(PWR_-12V-FB)") (class "Default")
      (node (ref "PWR_-12V") (pin "3") (pinfunction "FB_3") (pintype "bidirectional"))
      (node (ref "R3") (pin "P$2") (pinfunction "2_P$2") (pintype "bidirectional"))
      (node (ref "R4") (pin "P$1") (pinfunction "1_P$1") (pintype "bidirectional"))
    )
    (net (code "25") (name "Net-(PWR_-12V-OUT)") (class "Default")
      (node (ref "C14") (pin "1") (pinfunction "1_1") (pintype "bidirectional"))
      (node (ref "PWR_-12V") (pin "1") (pinfunction "OUT_1") (pintype "bidirectional"))
      (node (ref "R3") (pin "P$1") (pinfunction "1_P$1") (pintype "bidirectional"))
    )
    (net (code "26") (name "Net-(R1-1)") (class "Default")
      (node (ref "C2") (pin "1") (pinfunction "1_1") (pintype "bidirectional"))
      (node (ref "C3") (pin "1") (pinfunction "1_1") (pintype "bidirectional"))
      (node (ref "C4") (pin "1") (pinfunction "1_1") (pintype "bidirectional"))
      (node (ref "C5") (pin "1") (pinfunction "1_1") (pintype "bidirectional"))
      (node (ref "C6") (pin "1") (pinfunction "1_1") (pintype "bidirectional"))
      (node (ref "PWR_+12V") (pin "1") (pinfunction "OUT_1") (pintype "bidirectional"))
      (node (ref "R1") (pin "P$1") (pinfunction "1_P$1") (pintype "bidirectional"))
    )
    (net (code "27") (name "Net-(U2-LEFT)") (class "Default")
      (node (ref "L1") (pin "2") (pinfunction "2_2") (pintype "passive"))
      (node (ref "R7") (pin "2") (pinfunction "2_2") (pintype "bidirectional"))
      (node (ref "U2") (pin "TIP") (pinfunction "LEFT_TIP") (pintype "bidirectional"))
    )
    (net (code "28") (name "Net-(U2-RIGHT)") (class "Default")
      (node (ref "L2") (pin "2") (pinfunction "2_2") (pintype "passive"))
      (node (ref "R8") (pin "2") (pinfunction "2_2") (pintype "bidirectional"))
      (node (ref "U2") (pin "RING") (pinfunction "RIGHT_RING") (pintype "bidirectional"))
    )
    (net (code "29") (name "SD_A0") (class "Default")
      (node (ref "IC5") (pin "N6") (pinfunction "A0_N6") (pintype "input"))
    )
    (net (code "30") (name "SD_A1") (class "Default")
      (node (ref "IC5") (pin "P7") (pinfunction "A1_P7") (pintype "input"))
    )
    (net (code "31") (name "SD_A2") (class "Default")
      (node (ref "IC5") (pin "P6") (pinfunction "A2_P6") (pintype "input"))
    )
    (net (code "32") (name "SD_A3") (class "Default")
      (node (ref "IC5") (pin "R6") (pinfunction "A3_R6") (pintype "input"))
    )
    (net (code "33") (name "SD_A4") (class "Default")
      (node (ref "IC5") (pin "R2") (pinfunction "A4_R2") (pintype "input"))
    )
    (net (code "34") (name "SD_A5") (class "Default")
      (node (ref "IC5") (pin "P2") (pinfunction "A5_P2") (pintype "input"))
    )
    (net (code "35") (name "SD_A6") (class "Default")
      (node (ref "IC5") (pin "P1") (pinfunction "A6_P1") (pintype "input"))
    )
    (net (code "36") (name "SD_A7") (class "Default")
      (node (ref "IC5") (pin "N2") (pinfunction "A7_N2") (pintype "input"))
    )
    (net (code "37") (name "SD_A8") (class "Default")
      (node (ref "IC5") (pin "N1") (pinfunction "A8_N1") (pintype "input"))
    )
    (net (code "38") (name "SD_A9") (class "Default")
      (node (ref "IC5") (pin "M2") (pinfunction "A9_M2") (pintype "input"))
    )
    (net (code "39") (name "SD_A10") (class "Default")
      (node (ref "IC5") (pin "N7") (pinfunction "A10_N7") (pintype "input"))
    )
    (net (code "40") (name "SD_A11") (class "Default")
      (node (ref "IC5") (pin "M1") (pinfunction "A11_M1") (pintype "input"))
    )
    (net (code "41") (name "SD_CAS") (class "Default")
      (node (ref "IC5") (pin "K7") (pinfunction "~{CAS}_K7") (pintype "input"))
    )
    (net (code "42") (name "SD_CKE") (class "Default")
      (node (ref "IC5") (pin "L1") (pinfunction "CKE_L1") (pintype "input"))
    )
    (net (code "43") (name "SD_CLK") (class "Default")
      (node (ref "IC5") (pin "K2") (pinfunction "CLK_K2") (pintype "input"))
    )
    (net (code "44") (name "SD_CS") (class "Default")
      (node (ref "IC5") (pin "L7") (pinfunction "~{CS}_L7") (pintype "input"))
    )
    (net (code "45") (name "SD_D0") (class "Default")
      (node (ref "IC5") (pin "A6") (pinfunction "D0_A6") (pintype "bidirectional"))
    )
    (net (code "46") (name "SD_D1") (class "Default")
      (node (ref "IC5") (pin "B7") (pinfunction "D1_B7") (pintype "bidirectional"))
    )
    (net (code "47") (name "SD_D2") (class "Default")
      (node (ref "IC5") (pin "C7") (pinfunction "D2_C7") (pintype "bidirectional"))
    )
    (net (code "48") (name "SD_D3") (class "Default")
      (node (ref "IC5") (pin "D7") (pinfunction "D3_D7") (pintype "bidirectional"))
    )
    (net (code "49") (name "SD_D4") (class "Default")
      (node (ref "IC5") (pin "D6") (pinfunction "D4_D6") (pintype "bidirectional"))
    )
    (net (code "50") (name "SD_D5") (class "Default")
      (node (ref "IC5") (pin "E7") (pinfunction "D5_E7") (pintype "bidirectional"))
    )
    (net (code "51") (name "SD_D6") (class "Default")
      (node (ref "IC5") (pin "F7") (pinfunction "D6_F7") (pintype "bidirectional"))
    )
    (net (code "52") (name "SD_D7") (class "Default")
      (node (ref "IC5") (pin "G7") (pinfunction "D7_G7") (pintype "bidirectional"))
    )
    (net (code "53") (name "SD_D8") (class "Default")
      (node (ref "IC5") (pin "G1") (pinfunction "D8_G1") (pintype "bidirectional"))
    )
    (net (code "54") (name "SD_D9") (class "Default")
      (node (ref "IC5") (pin "F1") (pinfunction "D9_F1") (pintype "bidirectional"))
    )
    (net (code "55") (name "SD_D10") (class "Default")
      (node (ref "IC5") (pin "E1") (pinfunction "D10_E1") (pintype "bidirectional"))
    )
    (net (code "56") (name "SD_D11") (class "Default")
      (node (ref "IC5") (pin "D2") (pinfunction "D11_D2") (pintype "bidirectional"))
    )
    (net (code "57") (name "SD_D12") (class "Default")
      (node (ref "IC5") (pin "D1") (pinfunction "D12_D1") (pintype "bidirectional"))
    )
    (net (code "58") (name "SD_D13") (class "Default")
      (node (ref "IC5") (pin "C1") (pinfunction "D13_C1") (pintype "bidirectional"))
    )
    (net (code "59") (name "SD_D14") (class "Default")
      (node (ref "IC5") (pin "B1") (pinfunction "D14_B1") (pintype "bidirectional"))
    )
    (net (code "60") (name "SD_D15") (class "Default")
      (node (ref "IC5") (pin "A2") (pinfunction "D15_A2") (pintype "bidirectional"))
    )
    (net (code "61") (name "SD_LDQM") (class "Default")
      (node (ref "IC5") (pin "J6") (pinfunction "LDQM_J6") (pintype "input"))
    )
    (net (code "62") (name "SD_RAS") (class "Default")
      (node (ref "IC5") (pin "K6") (pinfunction "~{RAS}_K6") (pintype "input"))
    )
    (net (code "63") (name "SD_UDQM") (class "Default")
      (node (ref "IC5") (pin "J2") (pinfunction "UDQM_J2") (pintype "input"))
    )
    (net (code "64") (name "SD_WE") (class "Default")
      (node (ref "IC5") (pin "J7") (pinfunction "~{WE}_J7") (pintype "input"))
    )
    (net (code "65") (name "V+") (class "Default")
      (node (ref "OA2") (pin "8") (pinfunction "V+_8") (pintype "power_in"))
    )
    (net (code "66") (name "V-") (class "Default")
      (node (ref "OA2") (pin "4") (pinfunction "V-_4") (pintype "power_in"))
    )
    (net (code "67") (name "VBAT") (class "Default")
      (node (ref "C43") (pin "1") (pinfunction "1_1") (pintype "passive"))
      (node (ref "U$1") (pin "C1") (pinfunction "VBAT_C1") (pintype "bidirectional"))
    )
    (net (code "68") (name "VIN") (class "Default")
      (node (ref "C1") (pin "1") (pinfunction "1_1") (pintype "bidirectional"))
      (node (ref "C13") (pin "1") (pinfunction "1_1") (pintype "bidirectional"))
      (node (ref "C15") (pin "1") (pinfunction "1_1") (pintype "bidirectional"))
      (node (ref "C7") (pin "1") (pinfunction "1_1") (pintype "bidirectional"))
      (node (ref "PWR_+12V") (pin "15") (pinfunction "IN_15") (pintype "bidirectional"))
      (node (ref "PWR_-12V") (pin "15") (pinfunction "IN_15") (pintype "bidirectional"))
      (node (ref "PWR_3V3A") (pin "15") (pinfunction "IN_15") (pintype "bidirectional"))
      (node (ref "PWR_3V3D") (pin "13") (pinfunction "EN_13") (pintype "bidirectional"))
      (node (ref "PWR_3V3D") (pin "15") (pinfunction "IN_15") (pintype "bidirectional"))
    )
    (net (code "69") (name "unconnected-(DAC1-BCK-Pad13)") (class "Default")
      (node (ref "DAC1") (pin "13") (pinfunction "BCK_13") (pintype "bidirectional"))
    )
    (net (code "70") (name "unconnected-(DAC1-DEMP-Pad10)") (class "Default")
      (node (ref "DAC1") (pin "10") (pinfunction "DEMP_10") (pintype "bidirectional"))
    )
    (net (code "71") (name "unconnected-(DAC1-DIN-Pad14)") (class "Default")
      (node (ref "DAC1") (pin "14") (pinfunction "DIN_14") (pintype "bidirectional"))
    )
    (net (code "72") (name "unconnected-(DAC1-FLT-Pad11)") (class "Default")
      (node (ref "DAC1") (pin "11") (pinfunction "FLT_11") (pintype "bidirectional"))
    )
    (net (code "73") (name "unconnected-(DAC1-FMT-Pad16)") (class "Default")
      (node (ref "DAC1") (pin "16") (pinfunction "FMT_16") (pintype "bidirectional"))
    )
    (net (code "74") (name "unconnected-(DAC1-LRCK-Pad15)") (class "Default")
      (node (ref "DAC1") (pin "15") (pinfunction "LRCK_15") (pintype "bidirectional"))
    )
    (net (code "75") (name "unconnected-(DAC1-SCK-Pad12)") (class "Default")
      (node (ref "DAC1") (pin "12") (pinfunction "SCK_12") (pintype "bidirectional"))
    )
    (net (code "76") (name "unconnected-(DAC1-XSMT-Pad17)") (class "Default")
      (node (ref "DAC1") (pin "17") (pinfunction "XSMT_17") (pintype "bidirectional"))
    )
    (net (code "77") (name "unconnected-(OA2-PadTP)") (class "Default")
      (node (ref "OA2") (pin "TP") (pinfunction "TP_TP") (pintype "bidirectional"))
    )
    (net (code "78") (name "unconnected-(OA2A-INA+-Pad3)") (class "Default")
      (node (ref "OA2") (pin "3") (pinfunction "INA+_3") (pintype "bidirectional"))
    )
    (net (code "79") (name "unconnected-(OA2A-INA--Pad2)") (class "Default")
      (node (ref "OA2") (pin "2") (pinfunction "INA-_2") (pintype "bidirectional"))
    )
    (net (code "80") (name "unconnected-(OA2A-OUTA-Pad1)") (class "Default")
      (node (ref "OA2") (pin "1") (pinfunction "OUTA_1") (pintype "bidirectional"))
    )
    (net (code "81") (name "unconnected-(OA2B-INB+-Pad5)") (class "Default")
      (node (ref "OA2") (pin "5") (pinfunction "INB+_5") (pintype "bidirectional"))
    )
    (net (code "82") (name "unconnected-(OA2B-INB--Pad6)") (class "Default")
      (node (ref "OA2") (pin "6") (pinfunction "INB-_6") (pintype "bidirectional"))
    )
    (net (code "83") (name "unconnected-(OA2B-OUTB-Pad7)") (class "Default")
      (node (ref "OA2") (pin "7") (pinfunction "OUTB_7") (pintype "bidirectional"))
    )
    (net (code "84") (name "unconnected-(OA3A-IN+-Pad1)") (class "Default")
      (node (ref "OA3") (pin "1") (pinfunction "IN+_1") (pintype "bidirectional"))
    )
    (net (code "85") (name "unconnected-(OA3A-IN--Pad2)") (class "Default")
      (node (ref "OA3") (pin "2") (pinfunction "IN-_2") (pintype "bidirectional"))
    )
    (net (code "86") (name "unconnected-(OA3A-V+-Pad14)") (class "Default")
      (node (ref "OA3") (pin "14") (pinfunction "V+_14") (pintype "bidirectional"))
    )
    (net (code "87") (name "unconnected-(OA3A-V--Pad12)") (class "Default")
      (node (ref "OA3") (pin "12") (pinfunction "V-_12") (pintype "bidirectional"))
    )
    (net (code "88") (name "unconnected-(OA3B-IN+-Pad7)") (class "Default")
      (node (ref "OA3") (pin "7") (pinfunction "IN+_7") (pintype "bidirectional"))
    )
    (net (code "89") (name "unconnected-(OA3B-IN--Pad6)") (class "Default")
      (node (ref "OA3") (pin "6") (pinfunction "IN-_6") (pintype "bidirectional"))
    )
    (net (code "90") (name "unconnected-(OA3B-V+-Pad8)") (class "Default")
      (node (ref "OA3") (pin "8") (pinfunction "V+_8") (pintype "bidirectional"))
    )
    (net (code "91") (name "unconnected-(OA3B-V--Pad10)") (class "Default")
      (node (ref "OA3") (pin "10") (pinfunction "V-_10") (pintype "bidirectional"))
    )
    (net (code "92") (name "unconnected-(PWR_+12V-0P1V-Pad12)") (class "Default")
      (node (ref "PWR_+12V") (pin "12") (pinfunction "0P1V_12") (pintype "bidirectional"))
    )
    (net (code "93") (name "unconnected-(PWR_+12V-0P2V-Pad11)") (class "Default")
      (node (ref "PWR_+12V") (pin "11") (pinfunction "0P2V_11") (pintype "bidirectional"))
    )
    (net (code "94") (name "unconnected-(PWR_+12V-0P4V-Pad10)") (class "Default")
      (node (ref "PWR_+12V") (pin "10") (pinfunction "0P4V_10") (pintype "bidirectional"))
    )
    (net (code "95") (name "unconnected-(PWR_+12V-0P8V-Pad9)") (class "Default")
      (node (ref "PWR_+12V") (pin "9") (pinfunction "0P8V_9") (pintype "bidirectional"))
    )
    (net (code "96") (name "unconnected-(PWR_+12V-1P6V-Pad8)") (class "Default")
      (node (ref "PWR_+12V") (pin "8") (pinfunction "1P6V_8") (pintype "bidirectional"))
    )
    (net (code "97") (name "unconnected-(PWR_+12V-3P2V-Pad6)") (class "Default")
      (node (ref "PWR_+12V") (pin "6") (pinfunction "3P2V_6") (pintype "bidirectional"))
    )
    (net (code "98") (name "unconnected-(PWR_+12V-6P4V1-Pad5)") (class "Default")
      (node (ref "PWR_+12V") (pin "5") (pinfunction "6P4V1_5") (pintype "bidirectional"))
    )
    (net (code "99") (name "unconnected-(PWR_+12V-6P4V2-Pad4)") (class "Default")
      (node (ref "PWR_+12V") (pin "4") (pinfunction "6P4V2_4") (pintype "bidirectional"))
    )
    (net (code "100") (name "unconnected-(PWR_+12V-GND-Pad7)") (class "Default")
      (node (ref "PWR_+12V") (pin "7") (pinfunction "GND_7") (pintype "bidirectional"))
    )
    (net (code "101") (name "unconnected-(PWR_+12V-IN-Pad16)") (class "Default")
      (node (ref "PWR_+12V") (pin "16") (pinfunction "IN_16") (pintype "bidirectional"))
    )
    (net (code "102") (name "unconnected-(PWR_+12V-NC-Pad2)") (class "Default")
      (node (ref "PWR_+12V") (pin "2") (pinfunction "NC_2") (pintype "bidirectional"))
    )
    (net (code "103") (name "unconnected-(PWR_+12V-NC-Pad17)") (class "Default")
      (node (ref "PWR_+12V") (pin "17") (pinfunction "NC_17") (pintype "bidirectional"))
    )
    (net (code "104") (name "unconnected-(PWR_+12V-NC-Pad18)") (class "Default")
      (node (ref "PWR_+12V") (pin "18") (pinfunction "NC_18") (pintype "bidirectional"))
    )
    (net (code "105") (name "unconnected-(PWR_+12V-NC-Pad19)") (class "Default")
      (node (ref "PWR_+12V") (pin "19") (pinfunction "NC_19") (pintype "bidirectional"))
    )
    (net (code "106") (name "unconnected-(PWR_+12V-OUT-Pad20)") (class "Default")
      (node (ref "PWR_+12V") (pin "20") (pinfunction "OUT_20") (pintype "bidirectional"))
    )
    (net (code "107") (name "unconnected-(PWR_-12V-GND-Pad7)") (class "Default")
      (node (ref "PWR_-12V") (pin "7") (pinfunction "GND_7") (pintype "bidirectional"))
    )
    (net (code "108") (name "unconnected-(PWR_-12V-IN2-Pad16)") (class "Default")
      (node (ref "PWR_-12V") (pin "16") (pinfunction "IN2_16") (pintype "bidirectional"))
    )
    (net (code "109") (name "unconnected-(PWR_-12V-NC1-Pad2)") (class "Default")
      (node (ref "PWR_-12V") (pin "2") (pinfunction "NC1_2") (pintype "bidirectional"))
    )
    (net (code "110") (name "unconnected-(PWR_-12V-NC2-Pad4)") (class "Default")
      (node (ref "PWR_-12V") (pin "4") (pinfunction "NC2_4") (pintype "bidirectional"))
    )
    (net (code "111") (name "unconnected-(PWR_-12V-NC3-Pad5)") (class "Default")
      (node (ref "PWR_-12V") (pin "5") (pinfunction "NC3_5") (pintype "bidirectional"))
    )
    (net (code "112") (name "unconnected-(PWR_-12V-NC4-Pad6)") (class "Default")
      (node (ref "PWR_-12V") (pin "6") (pinfunction "NC4_6") (pintype "bidirectional"))
    )
    (net (code "113") (name "unconnected-(PWR_-12V-NC5-Pad8)") (class "Default")
      (node (ref "PWR_-12V") (pin "8") (pinfunction "NC5_8") (pintype "bidirectional"))
    )
    (net (code "114") (name "unconnected-(PWR_-12V-NC6-Pad9)") (class "Default")
      (node (ref "PWR_-12V") (pin "9") (pinfunction "NC6_9") (pintype "bidirectional"))
    )
    (net (code "115") (name "unconnected-(PWR_-12V-NC7-Pad10)") (class "Default")
      (node (ref "PWR_-12V") (pin "10") (pinfunction "NC7_10") (pintype "bidirectional"))
    )
    (net (code "116") (name "unconnected-(PWR_-12V-NC8-Pad11)") (class "Default")
      (node (ref "PWR_-12V") (pin "11") (pinfunction "NC8_11") (pintype "bidirectional"))
    )
    (net (code "117") (name "unconnected-(PWR_-12V-NC9-Pad12)") (class "Default")
      (node (ref "PWR_-12V") (pin "12") (pinfunction "NC9_12") (pintype "bidirectional"))
    )
    (net (code "118") (name "unconnected-(PWR_-12V-NC10-Pad17)") (class "Default")
      (node (ref "PWR_-12V") (pin "17") (pinfunction "NC10_17") (pintype "bidirectional"))
    )
    (net (code "119") (name "unconnected-(PWR_-12V-NC11-Pad18)") (class "Default")
      (node (ref "PWR_-12V") (pin "18") (pinfunction "NC11_18") (pintype "bidirectional"))
    )
    (net (code "120") (name "unconnected-(PWR_-12V-NC12-Pad19)") (class "Default")
      (node (ref "PWR_-12V") (pin "19") (pinfunction "NC12_19") (pintype "bidirectional"))
    )
    (net (code "121") (name "unconnected-(PWR_-12V-OUT2-Pad20)") (class "Default")
      (node (ref "PWR_-12V") (pin "20") (pinfunction "OUT2_20") (pintype "bidirectional"))
    )
    (net (code "122") (name "unconnected-(PWR_3V3A-0P4V-Pad10)") (class "Default")
      (node (ref "PWR_3V3A") (pin "10") (pinfunction "0P4V_10") (pintype "bidirectional"))
    )
    (net (code "123") (name "unconnected-(PWR_3V3A-0P8V-Pad9)") (class "Default")
      (node (ref "PWR_3V3A") (pin "9") (pinfunction "0P8V_9") (pintype "bidirectional"))
    )
    (net (code "124") (name "unconnected-(PWR_3V3A-3P2V-Pad6)") (class "Default")
      (node (ref "PWR_3V3A") (pin "6") (pinfunction "3P2V_6") (pintype "bidirectional"))
    )
    (net (code "125") (name "unconnected-(PWR_3V3A-6P4V1-Pad5)") (class "Default")
      (node (ref "PWR_3V3A") (pin "5") (pinfunction "6P4V1_5") (pintype "bidirectional"))
    )
    (net (code "126") (name "unconnected-(PWR_3V3A-6P4V2-Pad4)") (class "Default")
      (node (ref "PWR_3V3A") (pin "4") (pinfunction "6P4V2_4") (pintype "bidirectional"))
    )
    (net (code "127") (name "unconnected-(PWR_3V3A-GND-Pad7)") (class "Default")
      (node (ref "PWR_3V3A") (pin "7") (pinfunction "GND_7") (pintype "bidirectional"))
    )
    (net (code "128") (name "unconnected-(PWR_3V3A-IN-Pad16)") (class "Default")
      (node (ref "PWR_3V3A") (pin "16") (pinfunction "IN_16") (pintype "bidirectional"))
    )
    (net (code "129") (name "unconnected-(PWR_3V3A-NC-Pad2)") (class "Default")
      (node (ref "PWR_3V3A") (pin "2") (pinfunction "NC_2") (pintype "bidirectional"))
    )
    (net (code "130") (name "unconnected-(PWR_3V3A-NC-Pad17)") (class "Default")
      (node (ref "PWR_3V3A") (pin "17") (pinfunction "NC_17") (pintype "bidirectional"))
    )
    (net (code "131") (name "unconnected-(PWR_3V3A-NC-Pad18)") (class "Default")
      (node (ref "PWR_3V3A") (pin "18") (pinfunction "NC_18") (pintype "bidirectional"))
    )
    (net (code "132") (name "unconnected-(PWR_3V3A-NC-Pad19)") (class "Default")
      (node (ref "PWR_3V3A") (pin "19") (pinfunction "NC_19") (pintype "bidirectional"))
    )
    (net (code "133") (name "unconnected-(PWR_3V3A-OUT-Pad20)") (class "Default")
      (node (ref "PWR_3V3A") (pin "20") (pinfunction "OUT_20") (pintype "bidirectional"))
    )
    (net (code "134") (name "unconnected-(PWR_3V3A-SENSE{slash}FB-Pad3)") (class "Default")
      (node (ref "PWR_3V3A") (pin "3") (pinfunction "SENSE/FB_3") (pintype "bidirectional"))
    )
    (net (code "135") (name "unconnected-(PWR_3V3D-0P4V-Pad10)") (class "Default")
      (node (ref "PWR_3V3D") (pin "10") (pinfunction "0P4V_10") (pintype "bidirectional"))
    )
    (net (code "136") (name "unconnected-(PWR_3V3D-0P8V-Pad9)") (class "Default")
      (node (ref "PWR_3V3D") (pin "9") (pinfunction "0P8V_9") (pintype "bidirectional"))
    )
    (net (code "137") (name "unconnected-(PWR_3V3D-3P2V-Pad6)") (class "Default")
      (node (ref "PWR_3V3D") (pin "6") (pinfunction "3P2V_6") (pintype "bidirectional"))
    )
    (net (code "138") (name "unconnected-(PWR_3V3D-6P4V1-Pad5)") (class "Default")
      (node (ref "PWR_3V3D") (pin "5") (pinfunction "6P4V1_5") (pintype "bidirectional"))
    )
    (net (code "139") (name "unconnected-(PWR_3V3D-6P4V2-Pad4)") (class "Default")
      (node (ref "PWR_3V3D") (pin "4") (pinfunction "6P4V2_4") (pintype "bidirectional"))
    )
    (net (code "140") (name "unconnected-(PWR_3V3D-GND-Pad7)") (class "Default")
      (node (ref "PWR_3V3D") (pin "7") (pinfunction "GND_7") (pintype "bidirectional"))
    )
    (net (code "141") (name "unconnected-(PWR_3V3D-IN-Pad16)") (class "Default")
      (node (ref "PWR_3V3D") (pin "16") (pinfunction "IN_16") (pintype "bidirectional"))
    )
    (net (code "142") (name "unconnected-(PWR_3V3D-NC-Pad2)") (class "Default")
      (node (ref "PWR_3V3D") (pin "2") (pinfunction "NC_2") (pintype "bidirectional"))
    )
    (net (code "143") (name "unconnected-(PWR_3V3D-NC-Pad17)") (class "Default")
      (node (ref "PWR_3V3D") (pin "17") (pinfunction "NC_17") (pintype "bidirectional"))
    )
    (net (code "144") (name "unconnected-(PWR_3V3D-NC-Pad18)") (class "Default")
      (node (ref "PWR_3V3D") (pin "18") (pinfunction "NC_18") (pintype "bidirectional"))
    )
    (net (code "145") (name "unconnected-(PWR_3V3D-NC-Pad19)") (class "Default")
      (node (ref "PWR_3V3D") (pin "19") (pinfunction "NC_19") (pintype "bidirectional"))
    )
    (net (code "146") (name "unconnected-(PWR_3V3D-OUT-Pad20)") (class "Default")
      (node (ref "PWR_3V3D") (pin "20") (pinfunction "OUT_20") (pintype "bidirectional"))
    )
    (net (code "147") (name "unconnected-(PWR_3V3D-SENSE{slash}FB-Pad3)") (class "Default")
      (node (ref "PWR_3V3D") (pin "3") (pinfunction "SENSE/FB_3") (pintype "bidirectional"))
    )
    (net (code "148") (name "unconnected-(U$1-BOOT0-PadD6)") (class "Default")
      (node (ref "U$1") (pin "D6") (pinfunction "BOOT0_D6") (pintype "bidirectional"))
    )
    (net (code "149") (name "unconnected-(U$1-BYPASS_REG-PadL4)") (class "Default")
      (node (ref "U$1") (pin "L4") (pinfunction "BYPASS_REG_L4") (pintype "bidirectional"))
    )
    (net (code "150") (name "unconnected-(U$1-NRST-PadJ1)") (class "Default")
      (node (ref "U$1") (pin "J1") (pinfunction "NRST_J1") (pintype "bidirectional"))
    )
    (net (code "151") (name "unconnected-(U$1-PA0-PadN3)") (class "Default")
      (node (ref "U$1") (pin "N3") (pinfunction "PA0_N3") (pintype "bidirectional"))
    )
    (net (code "152") (name "unconnected-(U$1-PA1-PadN2)") (class "Default")
      (node (ref "U$1") (pin "N2") (pinfunction "PA1_N2") (pintype "bidirectional"))
    )
    (net (code "153") (name "unconnected-(U$1-PA2-PadP2)") (class "Default")
      (node (ref "U$1") (pin "P2") (pinfunction "PA2_P2") (pintype "bidirectional"))
    )
    (net (code "154") (name "unconnected-(U$1-PA3-PadR2)") (class "Default")
      (node (ref "U$1") (pin "R2") (pinfunction "PA3_R2") (pintype "bidirectional"))
    )
    (net (code "155") (name "unconnected-(U$1-PA4-PadN4)") (class "Default")
      (node (ref "U$1") (pin "N4") (pinfunction "PA4_N4") (pintype "bidirectional"))
    )
    (net (code "156") (name "unconnected-(U$1-PA5-PadP4)") (class "Default")
      (node (ref "U$1") (pin "P4") (pinfunction "PA5_P4") (pintype "bidirectional"))
    )
    (net (code "157") (name "unconnected-(U$1-PA6-PadP3)") (class "Default")
      (node (ref "U$1") (pin "P3") (pinfunction "PA6_P3") (pintype "bidirectional"))
    )
    (net (code "158") (name "unconnected-(U$1-PA7-PadR3)") (class "Default")
      (node (ref "U$1") (pin "R3") (pinfunction "PA7_R3") (pintype "bidirectional"))
    )
    (net (code "159") (name "unconnected-(U$1-PA8-PadF15)") (class "Default")
      (node (ref "U$1") (pin "F15") (pinfunction "PA8_F15") (pintype "bidirectional"))
    )
    (net (code "160") (name "unconnected-(U$1-PA9-PadE15)") (class "Default")
      (node (ref "U$1") (pin "E15") (pinfunction "PA9_E15") (pintype "bidirectional"))
    )
    (net (code "161") (name "unconnected-(U$1-PA10-PadD15)") (class "Default")
      (node (ref "U$1") (pin "D15") (pinfunction "PA10_D15") (pintype "bidirectional"))
    )
    (net (code "162") (name "unconnected-(U$1-PA11-PadC15)") (class "Default")
      (node (ref "U$1") (pin "C15") (pinfunction "PA11_C15") (pintype "bidirectional"))
    )
    (net (code "163") (name "unconnected-(U$1-PA12-PadB15)") (class "Default")
      (node (ref "U$1") (pin "B15") (pinfunction "PA12_B15") (pintype "bidirectional"))
    )
    (net (code "164") (name "unconnected-(U$1-PA13-PadA15)") (class "Default")
      (node (ref "U$1") (pin "A15") (pinfunction "PA13_A15") (pintype "bidirectional"))
    )
    (net (code "165") (name "unconnected-(U$1-PA14-PadA14)") (class "Default")
      (node (ref "U$1") (pin "A14") (pinfunction "PA14_A14") (pintype "bidirectional"))
    )
    (net (code "166") (name "unconnected-(U$1-PA15-PadA13)") (class "Default")
      (node (ref "U$1") (pin "A13") (pinfunction "PA15_A13") (pintype "bidirectional"))
    )
    (net (code "167") (name "unconnected-(U$1-PB0-PadR5)") (class "Default")
      (node (ref "U$1") (pin "R5") (pinfunction "PB0_R5") (pintype "bidirectional"))
    )
    (net (code "168") (name "unconnected-(U$1-PB1-PadR4)") (class "Default")
      (node (ref "U$1") (pin "R4") (pinfunction "PB1_R4") (pintype "bidirectional"))
    )
    (net (code "169") (name "unconnected-(U$1-PB2-PadM6)") (class "Default")
      (node (ref "U$1") (pin "M6") (pinfunction "PB2_M6") (pintype "bidirectional"))
    )
    (net (code "170") (name "unconnected-(U$1-PB3-PadA10)") (class "Default")
      (node (ref "U$1") (pin "A10") (pinfunction "PB3_A10") (pintype "bidirectional"))
    )
    (net (code "171") (name "unconnected-(U$1-PB4-PadA9)") (class "Default")
      (node (ref "U$1") (pin "A9") (pinfunction "PB4_A9") (pintype "bidirectional"))
    )
    (net (code "172") (name "unconnected-(U$1-PB5-PadA6)") (class "Default")
      (node (ref "U$1") (pin "A6") (pinfunction "PB5_A6") (pintype "bidirectional"))
    )
    (net (code "173") (name "unconnected-(U$1-PB6-PadB6)") (class "Default")
      (node (ref "U$1") (pin "B6") (pinfunction "PB6_B6") (pintype "bidirectional"))
    )
    (net (code "174") (name "unconnected-(U$1-PB7-PadB5)") (class "Default")
      (node (ref "U$1") (pin "B5") (pinfunction "PB7_B5") (pintype "bidirectional"))
    )
    (net (code "175") (name "unconnected-(U$1-PB8-PadA5)") (class "Default")
      (node (ref "U$1") (pin "A5") (pinfunction "PB8_A5") (pintype "bidirectional"))
    )
    (net (code "176") (name "unconnected-(U$1-PB9-PadB4)") (class "Default")
      (node (ref "U$1") (pin "B4") (pinfunction "PB9_B4") (pintype "bidirectional"))
    )
    (net (code "177") (name "unconnected-(U$1-PB10-PadR12)") (class "Default")
      (node (ref "U$1") (pin "R12") (pinfunction "PB10_R12") (pintype "bidirectional"))
    )
    (net (code "178") (name "unconnected-(U$1-PB11-PadR13)") (class "Default")
      (node (ref "U$1") (pin "R13") (pinfunction "PB11_R13") (pintype "bidirectional"))
    )
    (net (code "179") (name "unconnected-(U$1-PB12-PadP12)") (class "Default")
      (node (ref "U$1") (pin "P12") (pinfunction "PB12_P12") (pintype "bidirectional"))
    )
    (net (code "180") (name "unconnected-(U$1-PB13-PadP13)") (class "Default")
      (node (ref "U$1") (pin "P13") (pinfunction "PB13_P13") (pintype "bidirectional"))
    )
    (net (code "181") (name "unconnected-(U$1-PB14-PadR14)") (class "Default")
      (node (ref "U$1") (pin "R14") (pinfunction "PB14_R14") (pintype "bidirectional"))
    )
    (net (code "182") (name "unconnected-(U$1-PB15-PadR15)") (class "Default")
      (node (ref "U$1") (pin "R15") (pinfunction "PB15_R15") (pintype "bidirectional"))
    )
    (net (code "183") (name "unconnected-(U$1-PC0-PadM2)") (class "Default")
      (node (ref "U$1") (pin "M2") (pinfunction "PC0_M2") (pintype "bidirectional"))
    )
    (net (code "184") (name "unconnected-(U$1-PC1-PadM3)") (class "Default")
      (node (ref "U$1") (pin "M3") (pinfunction "PC1_M3") (pintype "bidirectional"))
    )
    (net (code "185") (name "unconnected-(U$1-PC2-PadM4)") (class "Default")
      (node (ref "U$1") (pin "M4") (pinfunction "PC2_M4") (pintype "bidirectional"))
    )
    (net (code "186") (name "unconnected-(U$1-PC3-PadM5)") (class "Default")
      (node (ref "U$1") (pin "M5") (pinfunction "PC3_M5") (pintype "bidirectional"))
    )
    (net (code "187") (name "unconnected-(U$1-PC4-PadN5)") (class "Default")
      (node (ref "U$1") (pin "N5") (pinfunction "PC4_N5") (pintype "bidirectional"))
    )
    (net (code "188") (name "unconnected-(U$1-PC5-PadP5)") (class "Default")
      (node (ref "U$1") (pin "P5") (pinfunction "PC5_P5") (pintype "bidirectional"))
    )
    (net (code "189") (name "unconnected-(U$1-PC6-PadH15)") (class "Default")
      (node (ref "U$1") (pin "H15") (pinfunction "PC6_H15") (pintype "bidirectional"))
    )
    (net (code "190") (name "unconnected-(U$1-PC7-PadG15)") (class "Default")
      (node (ref "U$1") (pin "G15") (pinfunction "PC7_G15") (pintype "bidirectional"))
    )
    (net (code "191") (name "unconnected-(U$1-PC8-PadG14)") (class "Default")
      (node (ref "U$1") (pin "G14") (pinfunction "PC8_G14") (pintype "bidirectional"))
    )
    (net (code "192") (name "unconnected-(U$1-PC9-PadF14)") (class "Default")
      (node (ref "U$1") (pin "F14") (pinfunction "PC9_F14") (pintype "bidirectional"))
    )
    (net (code "193") (name "unconnected-(U$1-PC10-PadB14)") (class "Default")
      (node (ref "U$1") (pin "B14") (pinfunction "PC10_B14") (pintype "bidirectional"))
    )
    (net (code "194") (name "unconnected-(U$1-PC11-PadB13)") (class "Default")
      (node (ref "U$1") (pin "B13") (pinfunction "PC11_B13") (pintype "bidirectional"))
    )
    (net (code "195") (name "unconnected-(U$1-PC12-PadA12)") (class "Default")
      (node (ref "U$1") (pin "A12") (pinfunction "PC12_A12") (pintype "bidirectional"))
    )
    (net (code "196") (name "unconnected-(U$1-PC13-PadD1)") (class "Default")
      (node (ref "U$1") (pin "D1") (pinfunction "PC13_D1") (pintype "bidirectional"))
    )
    (net (code "197") (name "unconnected-(U$1-PC14-PadE1)") (class "Default")
      (node (ref "U$1") (pin "E1") (pinfunction "PC14_E1") (pintype "bidirectional"))
    )
    (net (code "198") (name "unconnected-(U$1-PC15-PadF1)") (class "Default")
      (node (ref "U$1") (pin "F1") (pinfunction "PC15_F1") (pintype "bidirectional"))
    )
    (net (code "199") (name "unconnected-(U$1-PD0-PadB12)") (class "Default")
      (node (ref "U$1") (pin "B12") (pinfunction "PD0_B12") (pintype "bidirectional"))
    )
    (net (code "200") (name "unconnected-(U$1-PD1-PadC12)") (class "Default")
      (node (ref "U$1") (pin "C12") (pinfunction "PD1_C12") (pintype "bidirectional"))
    )
    (net (code "201") (name "unconnected-(U$1-PD2-PadD12)") (class "Default")
      (node (ref "U$1") (pin "D12") (pinfunction "PD2_D12") (pintype "bidirectional"))
    )
    (net (code "202") (name "unconnected-(U$1-PD3-PadD11)") (class "Default")
      (node (ref "U$1") (pin "D11") (pinfunction "PD3_D11") (pintype "bidirectional"))
    )
    (net (code "203") (name "unconnected-(U$1-PD4-PadD10)") (class "Default")
      (node (ref "U$1") (pin "D10") (pinfunction "PD4_D10") (pintype "bidirectional"))
    )
    (net (code "204") (name "unconnected-(U$1-PD5-PadC11)") (class "Default")
      (node (ref "U$1") (pin "C11") (pinfunction "PD5_C11") (pintype "bidirectional"))
    )
    (net (code "205") (name "unconnected-(U$1-PD6-PadB11)") (class "Default")
      (node (ref "U$1") (pin "B11") (pinfunction "PD6_B11") (pintype "bidirectional"))
    )
    (net (code "206") (name "unconnected-(U$1-PD7-PadA11)") (class "Default")
      (node (ref "U$1") (pin "A11") (pinfunction "PD7_A11") (pintype "bidirectional"))
    )
    (net (code "207") (name "unconnected-(U$1-PD8-PadP15)") (class "Default")
      (node (ref "U$1") (pin "P15") (pinfunction "PD8_P15") (pintype "bidirectional"))
    )
    (net (code "208") (name "unconnected-(U$1-PD9-PadP14)") (class "Default")
      (node (ref "U$1") (pin "P14") (pinfunction "PD9_P14") (pintype "bidirectional"))
    )
    (net (code "209") (name "unconnected-(U$1-PD10-PadN15)") (class "Default")
      (node (ref "U$1") (pin "N15") (pinfunction "PD10_N15") (pintype "bidirectional"))
    )
    (net (code "210") (name "unconnected-(U$1-PD11-PadN14)") (class "Default")
      (node (ref "U$1") (pin "N14") (pinfunction "PD11_N14") (pintype "bidirectional"))
    )
    (net (code "211") (name "unconnected-(U$1-PD12-PadN13)") (class "Default")
      (node (ref "U$1") (pin "N13") (pinfunction "PD12_N13") (pintype "bidirectional"))
    )
    (net (code "212") (name "unconnected-(U$1-PD13-PadM15)") (class "Default")
      (node (ref "U$1") (pin "M15") (pinfunction "PD13_M15") (pintype "bidirectional"))
    )
    (net (code "213") (name "unconnected-(U$1-PD14-PadM14)") (class "Default")
      (node (ref "U$1") (pin "M14") (pinfunction "PD14_M14") (pintype "bidirectional"))
    )
    (net (code "214") (name "unconnected-(U$1-PD15-PadL14)") (class "Default")
      (node (ref "U$1") (pin "L14") (pinfunction "PD15_L14") (pintype "bidirectional"))
    )
    (net (code "215") (name "unconnected-(U$1-PDR_ON-PadC6)") (class "Default")
      (node (ref "U$1") (pin "C6") (pinfunction "PDR_ON_C6") (pintype "bidirectional"))
    )
    (net (code "216") (name "unconnected-(U$1-PE0-PadA4)") (class "Default")
      (node (ref "U$1") (pin "A4") (pinfunction "PE0_A4") (pintype "bidirectional"))
    )
    (net (code "217") (name "unconnected-(U$1-PE1-PadA3)") (class "Default")
      (node (ref "U$1") (pin "A3") (pinfunction "PE1_A3") (pintype "bidirectional"))
    )
    (net (code "218") (name "unconnected-(U$1-PE2-PadA2)") (class "Default")
      (node (ref "U$1") (pin "A2") (pinfunction "PE2_A2") (pintype "bidirectional"))
    )
    (net (code "219") (name "unconnected-(U$1-PE3-PadA1)") (class "Default")
      (node (ref "U$1") (pin "A1") (pinfunction "PE3_A1") (pintype "bidirectional"))
    )
    (net (code "220") (name "unconnected-(U$1-PE4-PadB1)") (class "Default")
      (node (ref "U$1") (pin "B1") (pinfunction "PE4_B1") (pintype "bidirectional"))
    )
    (net (code "221") (name "unconnected-(U$1-PE5-PadB2)") (class "Default")
      (node (ref "U$1") (pin "B2") (pinfunction "PE5_B2") (pintype "bidirectional"))
    )
    (net (code "222") (name "unconnected-(U$1-PE6-PadB3)") (class "Default")
      (node (ref "U$1") (pin "B3") (pinfunction "PE6_B3") (pintype "bidirectional"))
    )
    (net (code "223") (name "unconnected-(U$1-PE7-PadR8)") (class "Default")
      (node (ref "U$1") (pin "R8") (pinfunction "PE7_R8") (pintype "bidirectional"))
    )
    (net (code "224") (name "unconnected-(U$1-PE8-PadP8)") (class "Default")
      (node (ref "U$1") (pin "P8") (pinfunction "PE8_P8") (pintype "bidirectional"))
    )
    (net (code "225") (name "unconnected-(U$1-PE9-PadP9)") (class "Default")
      (node (ref "U$1") (pin "P9") (pinfunction "PE9_P9") (pintype "bidirectional"))
    )
    (net (code "226") (name "unconnected-(U$1-PE10-PadR9)") (class "Default")
      (node (ref "U$1") (pin "R9") (pinfunction "PE10_R9") (pintype "bidirectional"))
    )
    (net (code "227") (name "unconnected-(U$1-PE11-PadP10)") (class "Default")
      (node (ref "U$1") (pin "P10") (pinfunction "PE11_P10") (pintype "bidirectional"))
    )
    (net (code "228") (name "unconnected-(U$1-PE12-PadR10)") (class "Default")
      (node (ref "U$1") (pin "R10") (pinfunction "PE12_R10") (pintype "bidirectional"))
    )
    (net (code "229") (name "unconnected-(U$1-PE13-PadN11)") (class "Default")
      (node (ref "U$1") (pin "N11") (pinfunction "PE13_N11") (pintype "bidirectional"))
    )
    (net (code "230") (name "unconnected-(U$1-PE14-PadP11)") (class "Default")
      (node (ref "U$1") (pin "P11") (pinfunction "PE14_P11") (pintype "bidirectional"))
    )
    (net (code "231") (name "unconnected-(U$1-PE15-PadR11)") (class "Default")
      (node (ref "U$1") (pin "R11") (pinfunction "PE15_R11") (pintype "bidirectional"))
    )
    (net (code "232") (name "unconnected-(U$1-PF0-PadE2)") (class "Default")
      (node (ref "U$1") (pin "E2") (pinfunction "PF0_E2") (pintype "bidirectional"))
    )
    (net (code "233") (name "unconnected-(U$1-PF1-PadH3)") (class "Default")
      (node (ref "U$1") (pin "H3") (pinfunction "PF1_H3") (pintype "bidirectional"))
    )
    (net (code "234") (name "unconnected-(U$1-PF2-PadH2)") (class "Default")
      (node (ref "U$1") (pin "H2") (pinfunction "PF2_H2") (pintype "bidirectional"))
    )
    (net (code "235") (name "unconnected-(U$1-PF3-PadJ2)") (class "Default")
      (node (ref "U$1") (pin "J2") (pinfunction "PF3_J2") (pintype "bidirectional"))
    )
    (net (code "236") (name "unconnected-(U$1-PF4-PadJ3)") (class "Default")
      (node (ref "U$1") (pin "J3") (pinfunction "PF4_J3") (pintype "bidirectional"))
    )
    (net (code "237") (name "unconnected-(U$1-PF5-PadK3)") (class "Default")
      (node (ref "U$1") (pin "K3") (pinfunction "PF5_K3") (pintype "bidirectional"))
    )
    (net (code "238") (name "unconnected-(U$1-PF6-PadK2)") (class "Default")
      (node (ref "U$1") (pin "K2") (pinfunction "PF6_K2") (pintype "bidirectional"))
    )
    (net (code "239") (name "unconnected-(U$1-PF7-PadK1)") (class "Default")
      (node (ref "U$1") (pin "K1") (pinfunction "PF7_K1") (pintype "bidirectional"))
    )
    (net (code "240") (name "unconnected-(U$1-PF8-PadL3)") (class "Default")
      (node (ref "U$1") (pin "L3") (pinfunction "PF8_L3") (pintype "bidirectional"))
    )
    (net (code "241") (name "unconnected-(U$1-PF9-PadL2)") (class "Default")
      (node (ref "U$1") (pin "L2") (pinfunction "PF9_L2") (pintype "bidirectional"))
    )
    (net (code "242") (name "unconnected-(U$1-PF10-PadL1)") (class "Default")
      (node (ref "U$1") (pin "L1") (pinfunction "PF10_L1") (pintype "bidirectional"))
    )
    (net (code "243") (name "unconnected-(U$1-PF11-PadR6)") (class "Default")
      (node (ref "U$1") (pin "R6") (pinfunction "PF11_R6") (pintype "bidirectional"))
    )
    (net (code "244") (name "unconnected-(U$1-PF12-PadP6)") (class "Default")
      (node (ref "U$1") (pin "P6") (pinfunction "PF12_P6") (pintype "bidirectional"))
    )
    (net (code "245") (name "unconnected-(U$1-PF13-PadN6)") (class "Default")
      (node (ref "U$1") (pin "N6") (pinfunction "PF13_N6") (pintype "bidirectional"))
    )
    (net (code "246") (name "unconnected-(U$1-PF14-PadR7)") (class "Default")
      (node (ref "U$1") (pin "R7") (pinfunction "PF14_R7") (pintype "bidirectional"))
    )
    (net (code "247") (name "unconnected-(U$1-PF15-PadP7)") (class "Default")
      (node (ref "U$1") (pin "P7") (pinfunction "PF15_P7") (pintype "bidirectional"))
    )
    (net (code "248") (name "unconnected-(U$1-PG0-PadN7)") (class "Default")
      (node (ref "U$1") (pin "N7") (pinfunction "PG0_N7") (pintype "bidirectional"))
    )
    (net (code "249") (name "unconnected-(U$1-PG1-PadM7)") (class "Default")
      (node (ref "U$1") (pin "M7") (pinfunction "PG1_M7") (pintype "bidirectional"))
    )
    (net (code "250") (name "unconnected-(U$1-PG2-PadL15)") (class "Default")
      (node (ref "U$1") (pin "L15") (pinfunction "PG2_L15") (pintype "bidirectional"))
    )
    (net (code "251") (name "unconnected-(U$1-PG3-PadK15)") (class "Default")
      (node (ref "U$1") (pin "K15") (pinfunction "PG3_K15") (pintype "bidirectional"))
    )
    (net (code "252") (name "unconnected-(U$1-PG4-PadK14)") (class "Default")
      (node (ref "U$1") (pin "K14") (pinfunction "PG4_K14") (pintype "bidirectional"))
    )
    (net (code "253") (name "unconnected-(U$1-PG5-PadK13)") (class "Default")
      (node (ref "U$1") (pin "K13") (pinfunction "PG5_K13") (pintype "bidirectional"))
    )
    (net (code "254") (name "unconnected-(U$1-PG6-PadJ15)") (class "Default")
      (node (ref "U$1") (pin "J15") (pinfunction "PG6_J15") (pintype "bidirectional"))
    )
    (net (code "255") (name "unconnected-(U$1-PG7-PadJ14)") (class "Default")
      (node (ref "U$1") (pin "J14") (pinfunction "PG7_J14") (pintype "bidirectional"))
    )
    (net (code "256") (name "unconnected-(U$1-PG8-PadH14)") (class "Default")
      (node (ref "U$1") (pin "H14") (pinfunction "PG8_H14") (pintype "bidirectional"))
    )
    (net (code "257") (name "unconnected-(U$1-PG9-PadC10)") (class "Default")
      (node (ref "U$1") (pin "C10") (pinfunction "PG9_C10") (pintype "bidirectional"))
    )
    (net (code "258") (name "unconnected-(U$1-PG10-PadB10)") (class "Default")
      (node (ref "U$1") (pin "B10") (pinfunction "PG10_B10") (pintype "bidirectional"))
    )
    (net (code "259") (name "unconnected-(U$1-PG11-PadB9)") (class "Default")
      (node (ref "U$1") (pin "B9") (pinfunction "PG11_B9") (pintype "bidirectional"))
    )
    (net (code "260") (name "unconnected-(U$1-PG12-PadB8)") (class "Default")
      (node (ref "U$1") (pin "B8") (pinfunction "PG12_B8") (pintype "bidirectional"))
    )
    (net (code "261") (name "unconnected-(U$1-PG13-PadA8)") (class "Default")
      (node (ref "U$1") (pin "A8") (pinfunction "PG13_A8") (pintype "bidirectional"))
    )
    (net (code "262") (name "unconnected-(U$1-PG14-PadA7)") (class "Default")
      (node (ref "U$1") (pin "A7") (pinfunction "PG14_A7") (pintype "bidirectional"))
    )
    (net (code "263") (name "unconnected-(U$1-PG15-PadB7)") (class "Default")
      (node (ref "U$1") (pin "B7") (pinfunction "PG15_B7") (pintype "bidirectional"))
    )
    (net (code "264") (name "unconnected-(U$1-PH0-PadG1)") (class "Default")
      (node (ref "U$1") (pin "G1") (pinfunction "PH0_G1") (pintype "bidirectional"))
    )
    (net (code "265") (name "unconnected-(U$1-PH1-PadH1)") (class "Default")
      (node (ref "U$1") (pin "H1") (pinfunction "PH1_H1") (pintype "bidirectional"))
    )
    (net (code "266") (name "unconnected-(U$1-PH2-PadF4)") (class "Default")
      (node (ref "U$1") (pin "F4") (pinfunction "PH2_F4") (pintype "bidirectional"))
    )
    (net (code "267") (name "unconnected-(U$1-PH3-PadG4)") (class "Default")
      (node (ref "U$1") (pin "G4") (pinfunction "PH3_G4") (pintype "bidirectional"))
    )
    (net (code "268") (name "unconnected-(U$1-PH4-PadH4)") (class "Default")
      (node (ref "U$1") (pin "H4") (pinfunction "PH4_H4") (pintype "bidirectional"))
    )
    (net (code "269") (name "unconnected-(U$1-PH5-PadJ4)") (class "Default")
      (node (ref "U$1") (pin "J4") (pinfunction "PH5_J4") (pintype "bidirectional"))
    )
    (net (code "270") (name "unconnected-(U$1-PH6-PadM11)") (class "Default")
      (node (ref "U$1") (pin "M11") (pinfunction "PH6_M11") (pintype "bidirectional"))
    )
    (net (code "271") (name "unconnected-(U$1-PH7-PadN12)") (class "Default")
      (node (ref "U$1") (pin "N12") (pinfunction "PH7_N12") (pintype "bidirectional"))
    )
    (net (code "272") (name "unconnected-(U$1-PH8-PadM12)") (class "Default")
      (node (ref "U$1") (pin "M12") (pinfunction "PH8_M12") (pintype "bidirectional"))
    )
    (net (code "273") (name "unconnected-(U$1-PH9-PadM13)") (class "Default")
      (node (ref "U$1") (pin "M13") (pinfunction "PH9_M13") (pintype "bidirectional"))
    )
    (net (code "274") (name "unconnected-(U$1-PH10-PadL13)") (class "Default")
      (node (ref "U$1") (pin "L13") (pinfunction "PH10_L13") (pintype "bidirectional"))
    )
    (net (code "275") (name "unconnected-(U$1-PH11-PadL12)") (class "Default")
      (node (ref "U$1") (pin "L12") (pinfunction "PH11_L12") (pintype "bidirectional"))
    )
    (net (code "276") (name "unconnected-(U$1-PH12-PadK12)") (class "Default")
      (node (ref "U$1") (pin "K12") (pinfunction "PH12_K12") (pintype "bidirectional"))
    )
    (net (code "277") (name "unconnected-(U$1-PH13-PadE12)") (class "Default")
      (node (ref "U$1") (pin "E12") (pinfunction "PH13_E12") (pintype "bidirectional"))
    )
    (net (code "278") (name "unconnected-(U$1-PH14-PadE13)") (class "Default")
      (node (ref "U$1") (pin "E13") (pinfunction "PH14_E13") (pintype "bidirectional"))
    )
    (net (code "279") (name "unconnected-(U$1-PH15-PadD13)") (class "Default")
      (node (ref "U$1") (pin "D13") (pinfunction "PH15_D13") (pintype "bidirectional"))
    )
    (net (code "280") (name "unconnected-(U$1-PI0-PadE14)") (class "Default")
      (node (ref "U$1") (pin "E14") (pinfunction "PI0_E14") (pintype "bidirectional"))
    )
    (net (code "281") (name "unconnected-(U$1-PI1-PadD14)") (class "Default")
      (node (ref "U$1") (pin "D14") (pinfunction "PI1_D14") (pintype "bidirectional"))
    )
    (net (code "282") (name "unconnected-(U$1-PI2-PadC14)") (class "Default")
      (node (ref "U$1") (pin "C14") (pinfunction "PI2_C14") (pintype "bidirectional"))
    )
    (net (code "283") (name "unconnected-(U$1-PI3-PadC13)") (class "Default")
      (node (ref "U$1") (pin "C13") (pinfunction "PI3_C13") (pintype "bidirectional"))
    )
    (net (code "284") (name "unconnected-(U$1-PI4-PadD4)") (class "Default")
      (node (ref "U$1") (pin "D4") (pinfunction "PI4_D4") (pintype "bidirectional"))
    )
    (net (code "285") (name "unconnected-(U$1-PI5-PadC4)") (class "Default")
      (node (ref "U$1") (pin "C4") (pinfunction "PI5_C4") (pintype "bidirectional"))
    )
    (net (code "286") (name "unconnected-(U$1-PI6-PadC3)") (class "Default")
      (node (ref "U$1") (pin "C3") (pinfunction "PI6_C3") (pintype "bidirectional"))
    )
    (net (code "287") (name "unconnected-(U$1-PI7-PadC2)") (class "Default")
      (node (ref "U$1") (pin "C2") (pinfunction "PI7_C2") (pintype "bidirectional"))
    )
    (net (code "288") (name "unconnected-(U$1-PI8-PadD2)") (class "Default")
      (node (ref "U$1") (pin "D2") (pinfunction "PI8_D2") (pintype "bidirectional"))
    )
    (net (code "289") (name "unconnected-(U$1-PI9-PadD3)") (class "Default")
      (node (ref "U$1") (pin "D3") (pinfunction "PI9_D3") (pintype "bidirectional"))
    )
    (net (code "290") (name "unconnected-(U$1-PI10-PadE3)") (class "Default")
      (node (ref "U$1") (pin "E3") (pinfunction "PI10_E3") (pintype "bidirectional"))
    )
    (net (code "291") (name "unconnected-(U$1-PI11-PadE4)") (class "Default")
      (node (ref "U$1") (pin "E4") (pinfunction "PI11_E4") (pintype "bidirectional"))
    )
    (net (code "292") (name "unconnected-(U$1-VCAP_1-PadM10)") (class "Default")
      (node (ref "U$1") (pin "M10") (pinfunction "VCAP_1_M10") (pintype "bidirectional"))
    )
    (net (code "293") (name "unconnected-(U$1-VCAP_2-PadF13)") (class "Default")
      (node (ref "U$1") (pin "F13") (pinfunction "VCAP_2_F13") (pintype "bidirectional"))
    )
    (net (code "294") (name "unconnected-(U$1-VREF+-PadP1)") (class "Default")
      (node (ref "U$1") (pin "P1") (pinfunction "VREF+_P1") (pintype "bidirectional"))
    )
    (net (code "295") (name "unconnected-(U$1-VREF--PadN1)") (class "Default")
      (node (ref "U$1") (pin "N1") (pinfunction "VREF-_N1") (pintype "bidirectional"))
    )
    (net (code "296") (name "unconnected-(U1-CS-Pad2)") (class "Default")
      (node (ref "U1") (pin "2") (pinfunction "CS_2") (pintype "bidirectional"))
    )
    (net (code "297") (name "unconnected-(U1-DI-Pad3)") (class "Default")
      (node (ref "U1") (pin "3") (pinfunction "DI_3") (pintype "bidirectional"))
    )
    (net (code "298") (name "unconnected-(U1-DO-Pad7)") (class "Default")
      (node (ref "U1") (pin "7") (pinfunction "DO_7") (pintype "bidirectional"))
    )
    (net (code "299") (name "unconnected-(U1-NC-Pad1)") (class "Default")
      (node (ref "U1") (pin "1") (pinfunction "NC_1") (pintype "bidirectional"))
    )
    (net (code "300") (name "unconnected-(U1-RSV-Pad8)") (class "Default")
      (node (ref "U1") (pin "8") (pinfunction "RSV_8") (pintype "bidirectional"))
    )
    (net (code "301") (name "unconnected-(U1-SCK-Pad5)") (class "Default")
      (node (ref "U1") (pin "5") (pinfunction "SCK_5") (pintype "bidirectional"))
    )
    (net (code "302") (name "unconnected-(U1-SHIELD-PadCD1)") (class "Default")
      (node (ref "U1") (pin "CD1") (pinfunction "SHIELD_CD1") (pintype "bidirectional"))
    )
    (net (code "303") (name "unconnected-(U1-SHIELD-PadCD2)") (class "Default")
      (node (ref "U1") (pin "CD2") (pinfunction "SHIELD_CD2") (pintype "bidirectional"))
    )
    (net (code "304") (name "unconnected-(U1-VCC-Pad4)") (class "Default")
      (node (ref "U1") (pin "4") (pinfunction "VCC_4") (pintype "bidirectional"))
    )
  )
)
